# Aquila-2019-ex.net
KiCad netlist of a schematic drawn in EAGLE
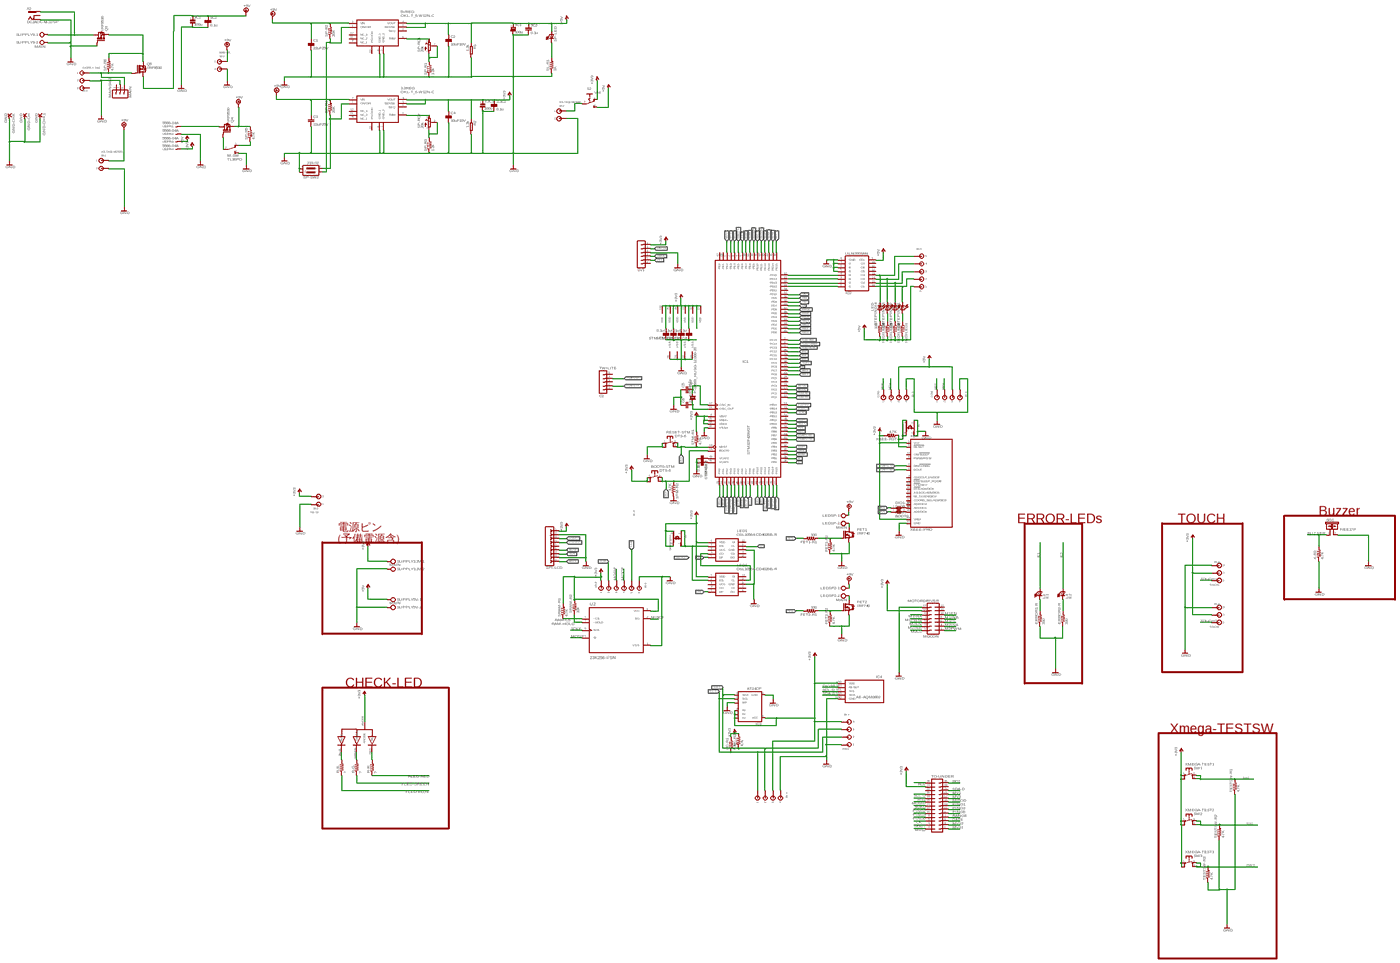
[diagram p0: schematic, sheet 1, overview]
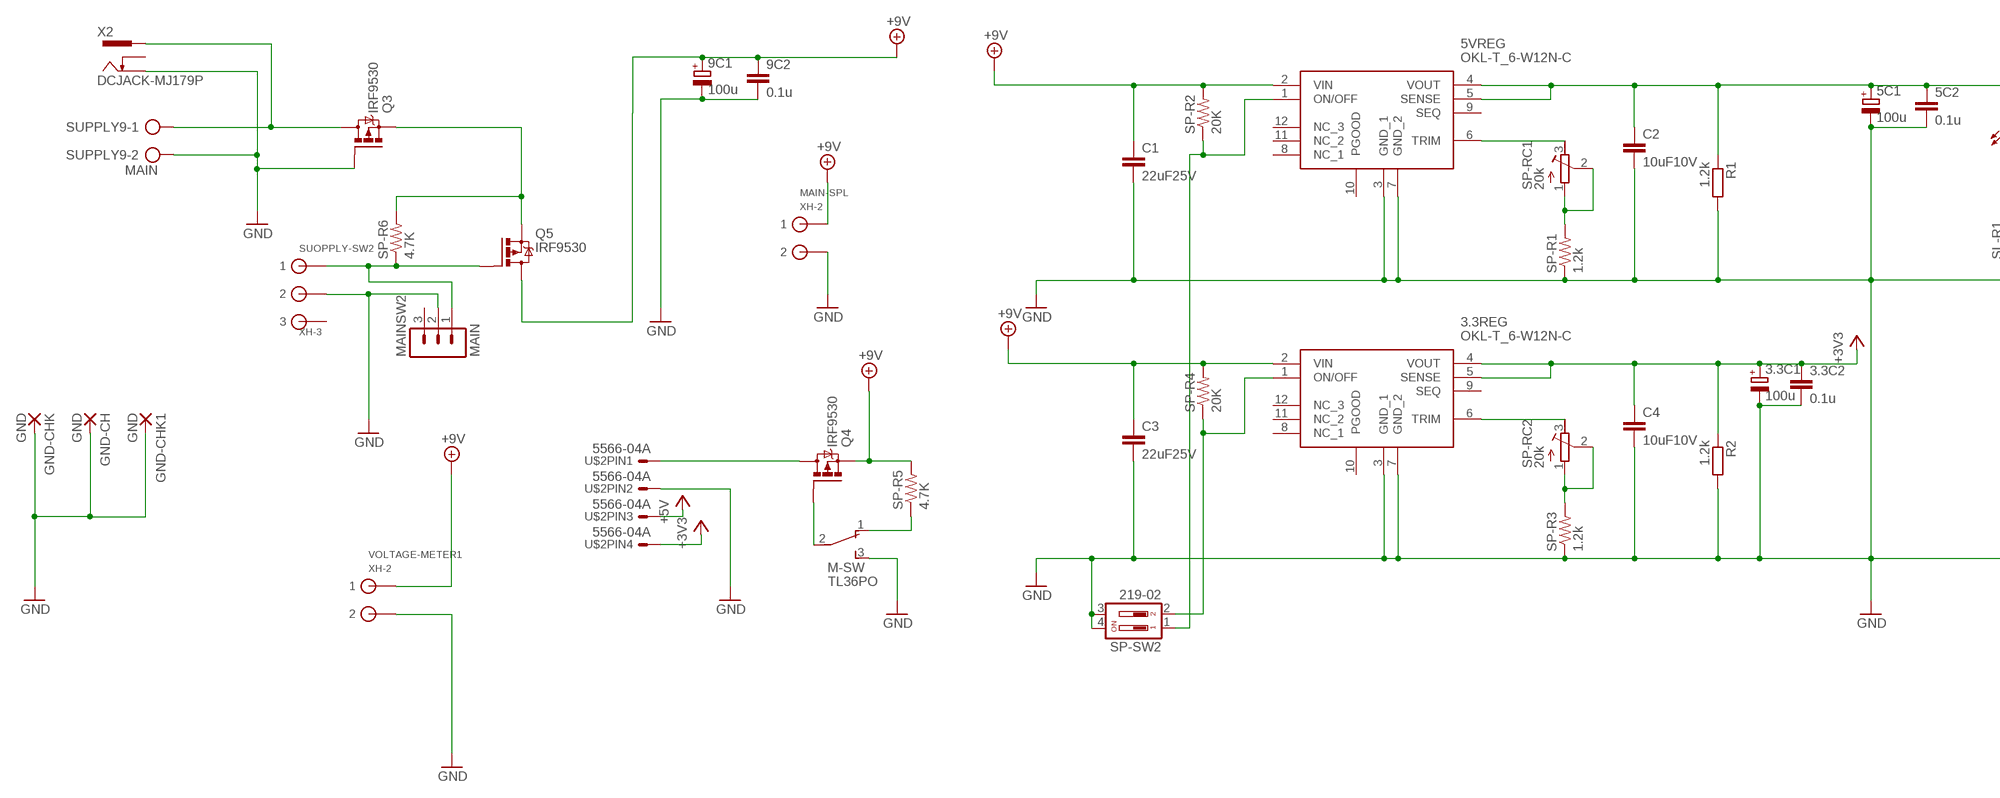
[diagram p1: schematic, sheet 1, part 1 of 5]
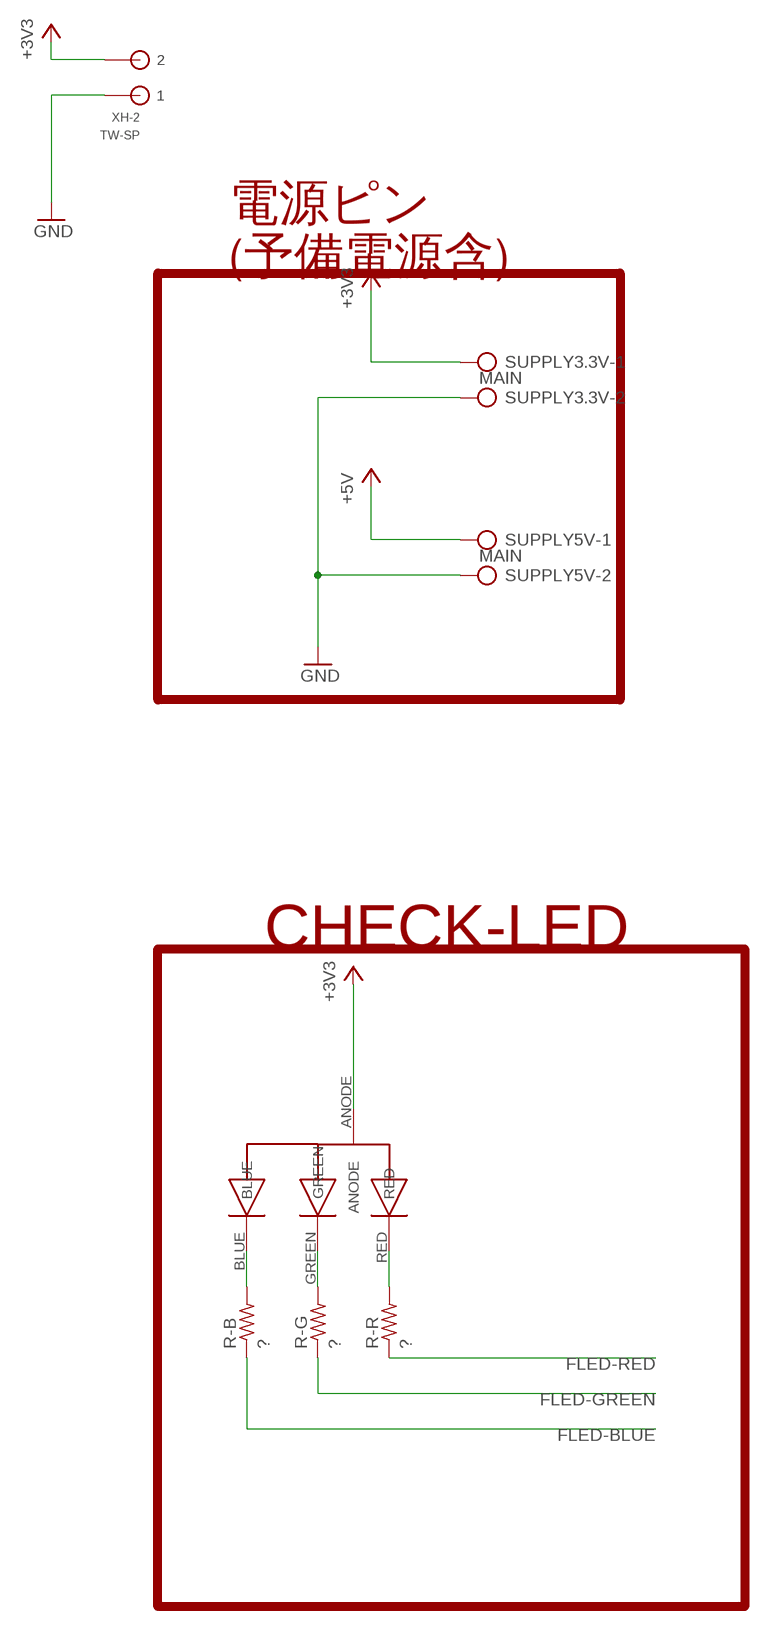
[diagram p2: schematic, sheet 1, part 2 of 5]
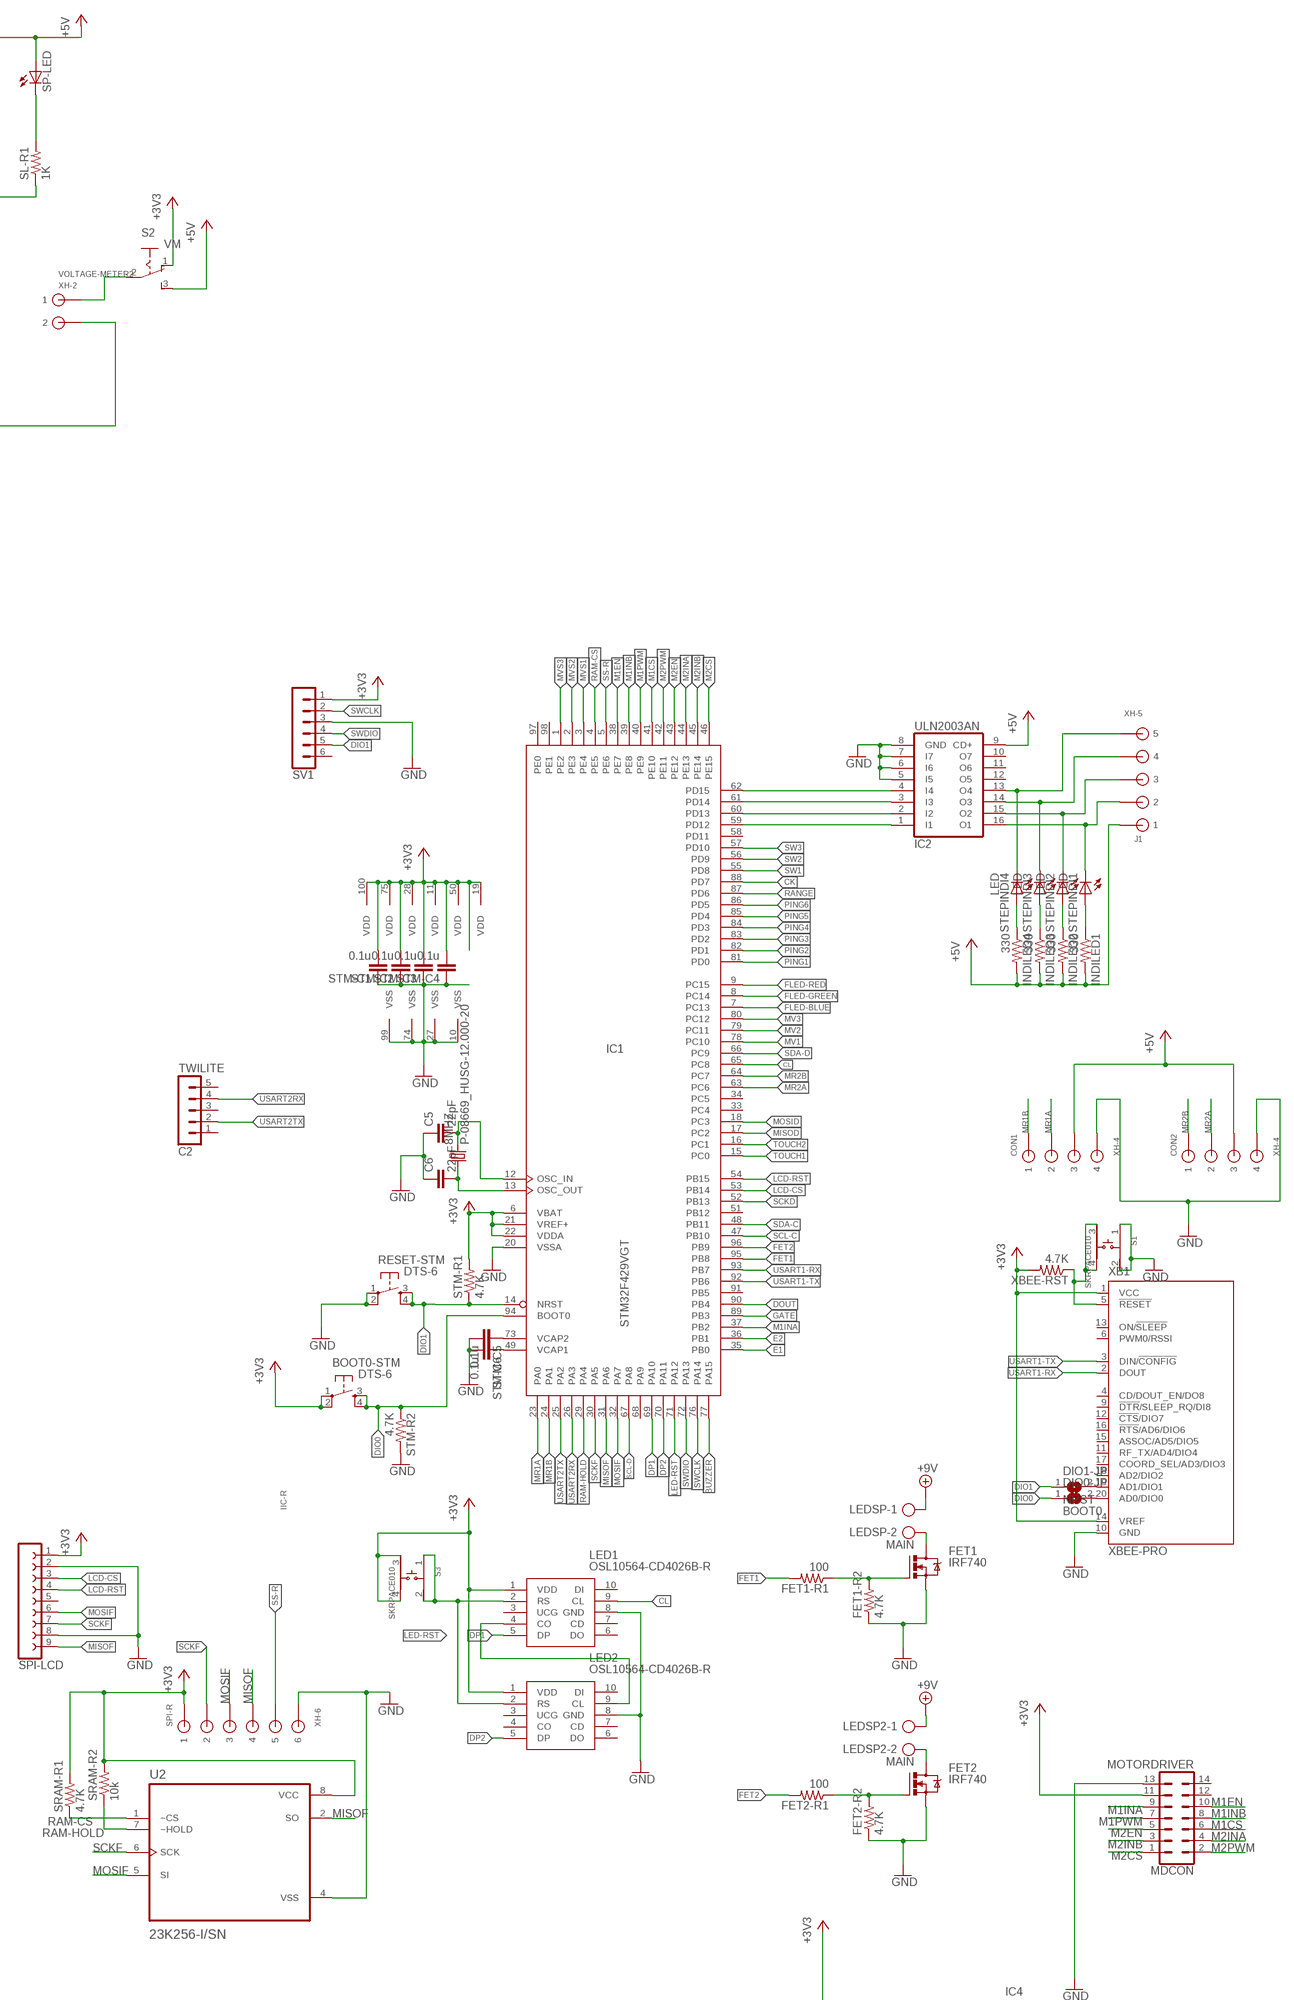
[diagram p3: schematic, sheet 1, part 3 of 5]
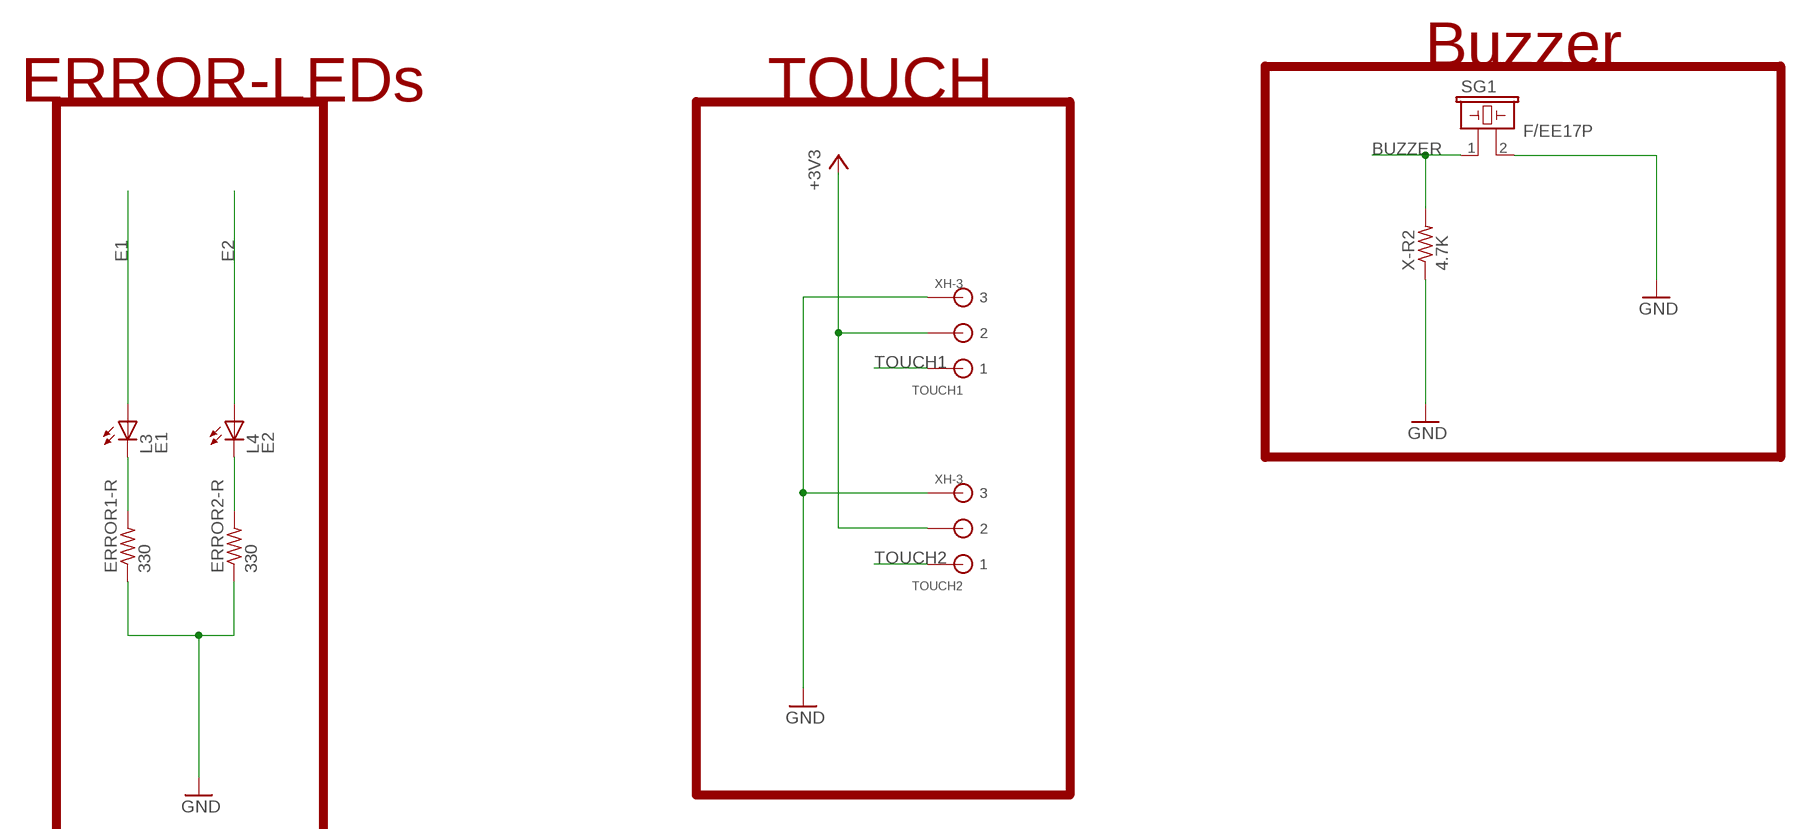
[diagram p4: schematic, sheet 1, part 4 of 5]
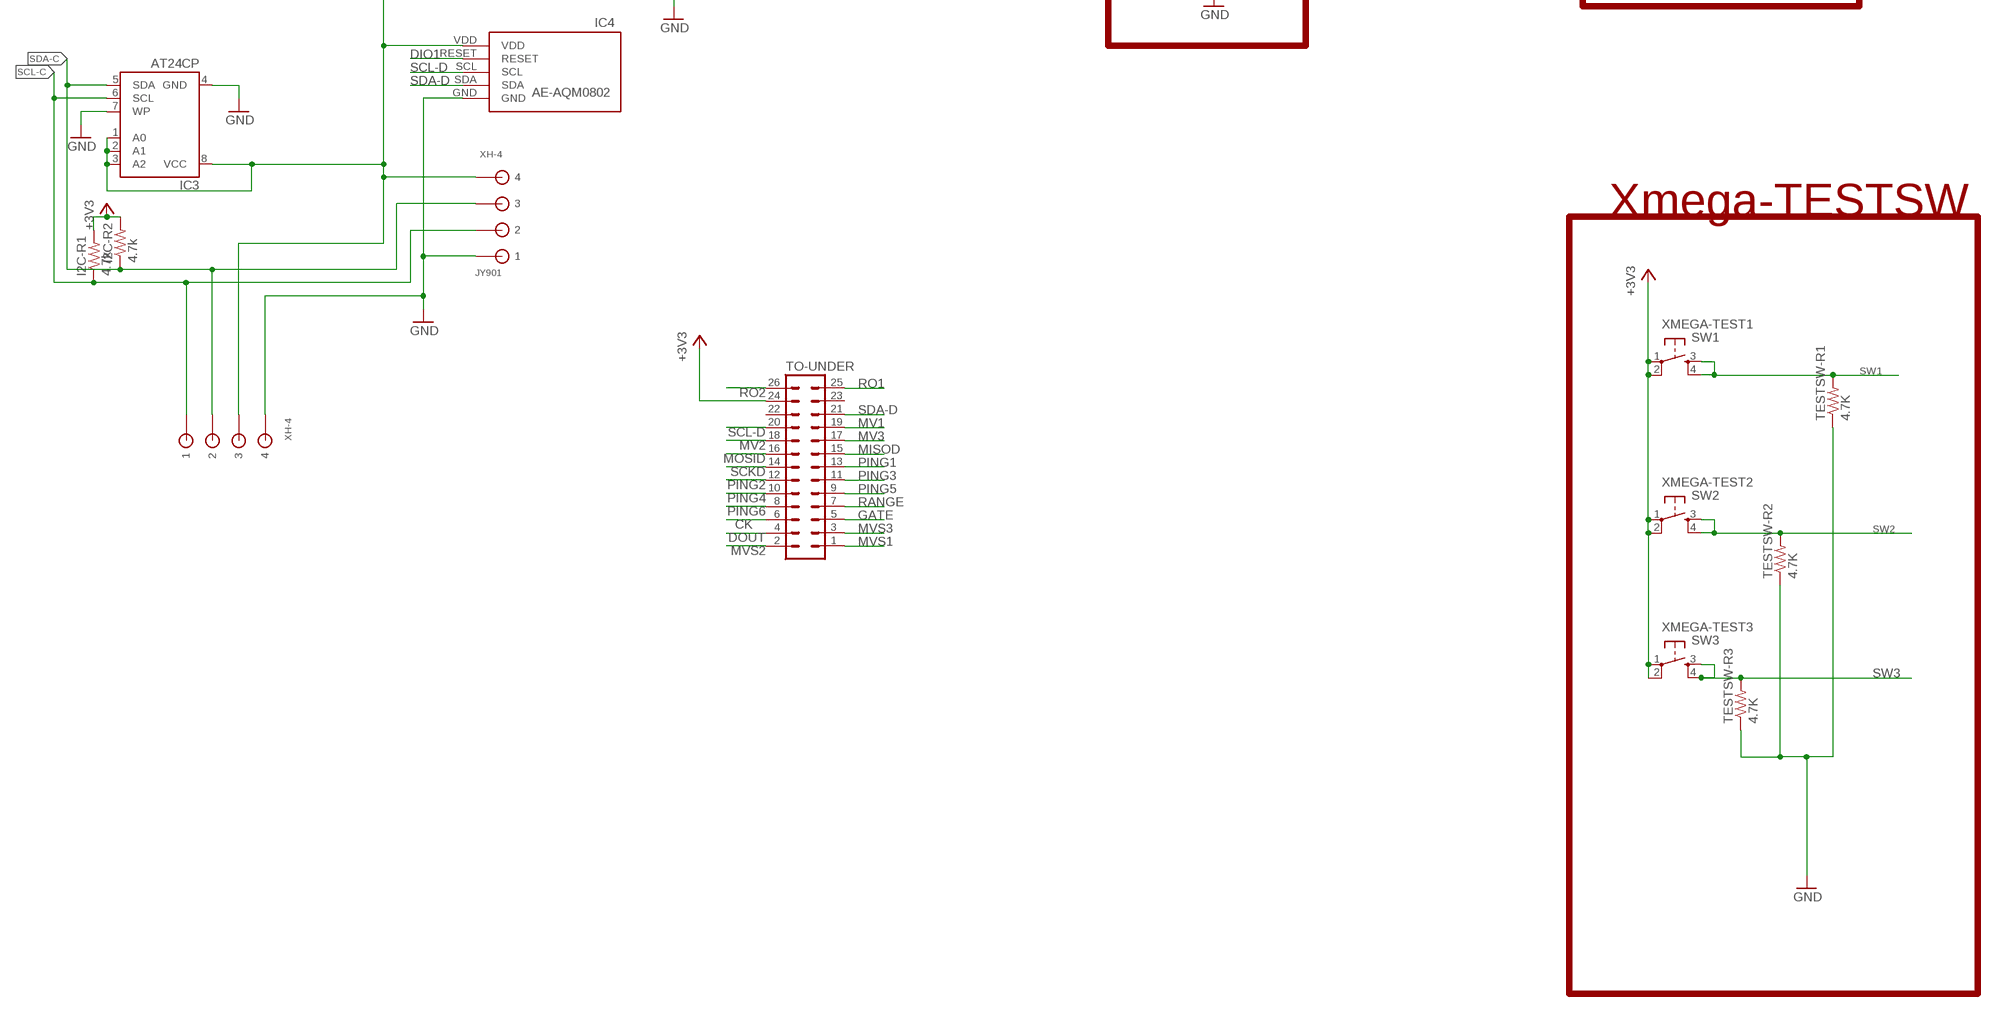
[diagram p5: schematic, sheet 1, part 5 of 5]

(export (version "E")
  (design (tool "Eeschema 10.0.6"))
  (components
    (comp (ref "3.3C1")
      (value "100u")
      (footprint "eagle-import:D_7343-31R")
      (fields (field (name "SPICEPREFIX") "B"))
      (libsource (lib "eagle-import") (part "CPOL-EUD/7343-31R"))
    )
    (comp (ref "3.3C2")
      (value "0.1u")
      (footprint "eagle-import:C0805")
      (fields (field (name "SPICEPREFIX") "B"))
      (libsource (lib "eagle-import") (part "C-EUC0805"))
    )
    (comp (ref "3.3REG")
      (value "OKL-T_6-W12N-C")
      (footprint "eagle-import:OKL-T_3-W5")
      (fields (field (name "ARROW_PART_NUMBER") "OKL-T/6-W12N-C") (field (name "RS_PART_NUMBER") "1736944P"))
      (libsource (lib "eagle-import") (part "OKL-T_6-W12N-C"))
    )
    (comp (ref "5C1")
      (value "100u")
      (footprint "eagle-import:D_7343-31R")
      (fields (field (name "SPICEPREFIX") "B"))
      (libsource (lib "eagle-import") (part "CPOL-EUD/7343-31R"))
    )
    (comp (ref "5C2")
      (value "0.1u")
      (footprint "eagle-import:C0805")
      (fields (field (name "SPICEPREFIX") "B"))
      (libsource (lib "eagle-import") (part "C-EUC0805"))
    )
    (comp (ref "5VREG")
      (value "OKL-T_6-W12N-C")
      (footprint "eagle-import:OKL-T_3-W5")
      (fields (field (name "ARROW_PART_NUMBER") "OKL-T/6-W12N-C") (field (name "RS_PART_NUMBER") "1736944P"))
      (libsource (lib "eagle-import") (part "OKL-T_6-W12N-C"))
    )
    (comp (ref "8MHZ")
      (value "P-08669_HUSG-12.000-20")
      (footprint "eagle-import:HC49U-V")
      (libsource (lib "eagle-import") (part "P-08669_HUSG-12.000-20"))
    )
    (comp (ref "9C1")
      (value "100u")
      (footprint "eagle-import:D_7343-31R")
      (fields (field (name "SPICEPREFIX") "B"))
      (libsource (lib "eagle-import") (part "CPOL-EUD/7343-31R"))
    )
    (comp (ref "9C2")
      (value "0.1u")
      (footprint "eagle-import:C0805")
      (fields (field (name "SPICEPREFIX") "B"))
      (libsource (lib "eagle-import") (part "C-EUC0805"))
    )
    (comp (ref "BOOT0-STM")
      (value "DTS-6")
      (footprint "eagle-import:DTS-6")
      (libsource (lib "eagle-import") (part "DTS-6"))
    )
    (comp (ref "C1")
      (value "22uF25V")
      (footprint "eagle-import:C2012")
      (libsource (lib "eagle-import") (part "resistor_348_C-EUC2012"))
    )
    (comp (ref "C2")
      (value "10uF10V")
      (footprint "eagle-import:C2012")
      (libsource (lib "eagle-import") (part "resistor_348_C-EUC2012"))
    )
    (comp (ref "C3")
      (value "22uF25V")
      (footprint "eagle-import:C2012")
      (libsource (lib "eagle-import") (part "resistor_348_C-EUC2012"))
    )
    (comp (ref "C4")
      (value "10uF10V")
      (footprint "eagle-import:C2012")
      (libsource (lib "eagle-import") (part "resistor_348_C-EUC2012"))
    )
    (comp (ref "C5")
      (value "22pF")
      (footprint "eagle-import:C1608")
      (libsource (lib "eagle-import") (part "resistor_348_C-EUC1608"))
    )
    (comp (ref "C6")
      (value "22pF")
      (footprint "eagle-import:C1608")
      (libsource (lib "eagle-import") (part "resistor_348_C-EUC1608"))
    )
    (comp (ref "CHECKLED")
      (value "OSTA71A1D-A")
      (footprint "eagle-import:OSTA71A1D-A")
      (libsource (lib "eagle-import") (part "OSTA71A1D-A"))
    )
    (comp (ref "CON1")
      (value "XH-4")
      (footprint "eagle-import:CON4")
      (libsource (lib "eagle-import") (part "XH-4"))
    )
    (comp (ref "CON2")
      (value "XH-4")
      (footprint "eagle-import:CON4")
      (libsource (lib "eagle-import") (part "XH-4"))
    )
    (comp (ref "DIO0-JP")
      (value "BOOT0")
      (footprint "eagle-import:SJ")
      (libsource (lib "eagle-import") (part "SJ"))
    )
    (comp (ref "DIO1-JP")
      (value "NRST")
      (footprint "eagle-import:SJ")
      (libsource (lib "eagle-import") (part "SJ"))
    )
    (comp (ref "ERROR1-R")
      (value "330")
      (footprint "eagle-import:R0805")
      (libsource (lib "eagle-import") (part "R-US_R0805"))
    )
    (comp (ref "ERROR2-R")
      (value "330")
      (footprint "eagle-import:R0805")
      (libsource (lib "eagle-import") (part "R-US_R0805"))
    )
    (comp (ref "FET1")
      (value "IRF740")
      (footprint "eagle-import:TO220BV")
      (libsource (lib "eagle-import") (part "IRF740"))
    )
    (comp (ref "FET1-R1")
      (value "100")
      (footprint "eagle-import:R0805")
      (libsource (lib "eagle-import") (part "R-US_R0805"))
    )
    (comp (ref "FET1-R2")
      (value "4.7K")
      (footprint "eagle-import:R0805")
      (libsource (lib "eagle-import") (part "R-US_R0805"))
    )
    (comp (ref "FET2")
      (value "IRF740")
      (footprint "eagle-import:TO220BV")
      (libsource (lib "eagle-import") (part "IRF740"))
    )
    (comp (ref "FET2-R1")
      (value "100")
      (footprint "eagle-import:R0805")
      (libsource (lib "eagle-import") (part "R-US_R0805"))
    )
    (comp (ref "FET2-R2")
      (value "4.7K")
      (footprint "eagle-import:R0805")
      (libsource (lib "eagle-import") (part "R-US_R0805"))
    )
    (comp (ref "GND-CH")
      (value "GND")
      (footprint "eagle-import:SMD2,54-5,08")
      (libsource (lib "eagle-import") (part "SMD5"))
    )
    (comp (ref "GND-CHK")
      (value "GND")
      (footprint "eagle-import:2,15_1,0")
      (libsource (lib "eagle-import") (part "2,15/1,0"))
    )
    (comp (ref "GND-CHK1")
      (value "GND")
      (footprint "eagle-import:2,15_1,0")
      (libsource (lib "eagle-import") (part "2,15/1,0"))
    )
    (comp (ref "I2C-R1")
      (value "4.7k")
      (footprint "eagle-import:R0805")
      (libsource (lib "eagle-import") (part "R-US_R0805"))
    )
    (comp (ref "I2C-R2")
      (value "4.7k")
      (footprint "eagle-import:R0805")
      (libsource (lib "eagle-import") (part "R-US_R0805"))
    )
    (comp (ref "IC1")
      (value "STM32F429VGT")
      (footprint "eagle-import:LQFP100")
      (libsource (lib "eagle-import") (part "STM32F429VTG"))
    )
    (comp (ref "IC2")
      (value "ULN2003AN")
      (footprint "eagle-import:DIL16")
      (fields (field (name "MF") "STMicroelectronics") (field (name "MP") "ULN2003A"))
      (libsource (lib "eagle-import") (part "ULN2003AN"))
    )
    (comp (ref "IC3")
      (value "AT24CP")
      (footprint "eagle-import:DIL08")
      (fields (field (name "MPN") "AT24C1024BW-SH-B"))
      (libsource (lib "eagle-import") (part "AT24CP"))
    )
    (comp (ref "IC4")
      (value "AE-AQM0802")
      (footprint "eagle-import:AE-AQM0802")
      (libsource (lib "eagle-import") (part "AE-AQM0802"))
    )
    (comp (ref "IIC-R")
      (value "XH-4")
      (footprint "eagle-import:CON4")
      (libsource (lib "eagle-import") (part "XH-4"))
    )
    (comp (ref "INDILED1")
      (value "330")
      (footprint "eagle-import:R0805")
      (libsource (lib "eagle-import") (part "R-US_R0805"))
    )
    (comp (ref "INDILED2")
      (value "330")
      (footprint "eagle-import:R0805")
      (libsource (lib "eagle-import") (part "R-US_R0805"))
    )
    (comp (ref "INDILED3")
      (value "330")
      (footprint "eagle-import:R0805")
      (libsource (lib "eagle-import") (part "R-US_R0805"))
    )
    (comp (ref "INDILED4")
      (value "330")
      (footprint "eagle-import:R0805")
      (libsource (lib "eagle-import") (part "R-US_R0805"))
    )
    (comp (ref "J1")
      (value "XH-5")
      (footprint "eagle-import:CON5")
      (libsource (lib "eagle-import") (part "XH-5"))
    )
    (comp (ref "JY901")
      (value "XH-4")
      (footprint "eagle-import:CON4")
      (libsource (lib "eagle-import") (part "XH-4"))
    )
    (comp (ref "L3")
      (value "E1")
      (footprint "eagle-import:LED5MM")
      (libsource (lib "eagle-import") (part "LED5MM"))
    )
    (comp (ref "L4")
      (value "E2")
      (footprint "eagle-import:LED5MM")
      (libsource (lib "eagle-import") (part "LED5MM"))
    )
    (comp (ref "LED1")
      (value "OSL10564-CD4026B-R")
      (footprint "eagle-import:DIPS1524W50P254L1260H800Q10N")
      (libsource (lib "eagle-import") (part "OSL10564-CD4026B-R"))
    )
    (comp (ref "LED2")
      (value "OSL10564-CD4026B-R")
      (footprint "eagle-import:DIPS1524W50P254L1260H800Q10N")
      (libsource (lib "eagle-import") (part "OSL10564-CD4026B-R"))
    )
    (comp (ref "LEDSP")
      (value "MAIN")
      (footprint "eagle-import:AK500_2")
      (libsource (lib "eagle-import") (part "AK500/2"))
    )
    (comp (ref "LEDSP2")
      (value "MAIN")
      (footprint "eagle-import:AK500_2")
      (libsource (lib "eagle-import") (part "AK500/2"))
    )
    (comp (ref "M-SW")
      (value "TL36PO")
      (footprint "eagle-import:TL3XPO")
      (libsource (lib "eagle-import") (part "TL36PO"))
    )
    (comp (ref "MAIN-SPL")
      (value "XH-2")
      (footprint "eagle-import:CON2")
      (libsource (lib "eagle-import") (part "forprint_XH-2"))
    )
    (comp (ref "MAINSW2")
      (value "MAIN")
      (footprint "eagle-import:MA03-1")
      (libsource (lib "eagle-import") (part "MA03-1"))
    )
    (comp (ref "MOTORDRIVER")
      (value "MDCON")
      (footprint "eagle-import:ML14")
      (libsource (lib "eagle-import") (part "ML14"))
    )
    (comp (ref "Q3")
      (value "IRF9530")
      (footprint "eagle-import:TO220BV")
      (libsource (lib "eagle-import") (part "IRF9530"))
    )
    (comp (ref "Q4")
      (value "IRF9530")
      (footprint "eagle-import:TO220BV")
      (libsource (lib "eagle-import") (part "IRF9530"))
    )
    (comp (ref "Q5")
      (value "IRF9530")
      (footprint "eagle-import:TO220BV")
      (libsource (lib "eagle-import") (part "IRF9530"))
    )
    (comp (ref "R-B")
      (value "?")
      (footprint "eagle-import:R0805")
      (libsource (lib "eagle-import") (part "R-US_R0805"))
    )
    (comp (ref "R-G")
      (value "?")
      (footprint "eagle-import:R0805")
      (libsource (lib "eagle-import") (part "R-US_R0805"))
    )
    (comp (ref "R-R")
      (value "?")
      (footprint "eagle-import:R0805")
      (libsource (lib "eagle-import") (part "R-US_R0805"))
    )
    (comp (ref "R1")
      (value "1.2k")
      (footprint "eagle-import:0204_7")
      (libsource (lib "eagle-import") (part "R-EU_0204/7"))
    )
    (comp (ref "R2")
      (value "1.2k")
      (footprint "eagle-import:0204_7")
      (libsource (lib "eagle-import") (part "R-EU_0204/7"))
    )
    (comp (ref "RESET-STM")
      (value "DTS-6")
      (footprint "eagle-import:DTS-6")
      (libsource (lib "eagle-import") (part "DTS-6"))
    )
    (comp (ref "S1")
      (value "SKRPACE010")
      (footprint "eagle-import:SW_SKRPACE010")
      (fields (field (name "MF") "ALPS"))
      (libsource (lib "eagle-import") (part "SKRPACE010"))
    )
    (comp (ref "S2")
      (value "VM")
      (footprint "eagle-import:M251")
      (libsource (lib "eagle-import") (part "M251"))
    )
    (comp (ref "S3")
      (value "SKRPACE010")
      (footprint "eagle-import:SW_SKRPACE010")
      (fields (field (name "MF") "ALPS"))
      (libsource (lib "eagle-import") (part "SKRPACE010"))
    )
    (comp (ref "SG1")
      (value "F/EE17P")
      (footprint "eagle-import:F_EE17P")
      (libsource (lib "eagle-import") (part "F/EE17P"))
    )
    (comp (ref "SL-R1")
      (value "1K")
      (footprint "eagle-import:R0805")
      (libsource (lib "eagle-import") (part "R-US_R0805"))
    )
    (comp (ref "SP-LED")
      (value "LEDCHIPLED_0805")
      (footprint "eagle-import:CHIPLED_0805")
      (libsource (lib "eagle-import") (part "led_LEDCHIPLED_0805"))
    )
    (comp (ref "SP-R1")
      (value "1.2k")
      (footprint "eagle-import:R0805")
      (libsource (lib "eagle-import") (part "R-US_R0805"))
    )
    (comp (ref "SP-R2")
      (value "20K")
      (footprint "eagle-import:R0805")
      (libsource (lib "eagle-import") (part "R-US_R0805"))
    )
    (comp (ref "SP-R3")
      (value "1.2k")
      (footprint "eagle-import:R0805")
      (libsource (lib "eagle-import") (part "R-US_R0805"))
    )
    (comp (ref "SP-R4")
      (value "20K")
      (footprint "eagle-import:R0805")
      (libsource (lib "eagle-import") (part "R-US_R0805"))
    )
    (comp (ref "SP-R5")
      (value "4.7K")
      (footprint "eagle-import:R0805")
      (libsource (lib "eagle-import") (part "R-US_R0805"))
    )
    (comp (ref "SP-R6")
      (value "4.7K")
      (footprint "eagle-import:R0805")
      (libsource (lib "eagle-import") (part "R-US_R0805"))
    )
    (comp (ref "SP-RC1")
      (value "20k")
      (footprint "eagle-import:RTRIM3296W")
      (libsource (lib "eagle-import") (part "R-TRIMM3296W"))
    )
    (comp (ref "SP-RC2")
      (value "20k")
      (footprint "eagle-import:RTRIM3296W")
      (libsource (lib "eagle-import") (part "R-TRIMM3296W"))
    )
    (comp (ref "SP-SW2")
      (value "219-02")
      (footprint "eagle-import:CTS-219-02")
      (libsource (lib "eagle-import") (part "219-02"))
    )
    (comp (ref "SPI-LCD")
      (value "FE09-1")
      (footprint "eagle-import:FE09")
      (libsource (lib "eagle-import") (part "FE09-1"))
    )
    (comp (ref "SPI-R")
      (value "XH-6")
      (footprint "eagle-import:CON6")
      (libsource (lib "eagle-import") (part "XH-6"))
    )
    (comp (ref "SRAM-R1")
      (value "4.7K")
      (footprint "eagle-import:R0805")
      (libsource (lib "eagle-import") (part "R-US_R0805"))
    )
    (comp (ref "SRAM-R2")
      (value "10k")
      (footprint "eagle-import:R0805")
      (libsource (lib "eagle-import") (part "R-US_R0805"))
    )
    (comp (ref "STEPINDI1")
      (value "LED")
      (footprint "eagle-import:CHIPLED_0805")
      (libsource (lib "eagle-import") (part "led_LEDCHIPLED_0805"))
    )
    (comp (ref "STEPINDI2")
      (value "LED")
      (footprint "eagle-import:CHIPLED_0805")
      (libsource (lib "eagle-import") (part "led_LEDCHIPLED_0805"))
    )
    (comp (ref "STEPINDI3")
      (value "LED")
      (footprint "eagle-import:CHIPLED_0805")
      (libsource (lib "eagle-import") (part "led_LEDCHIPLED_0805"))
    )
    (comp (ref "STEPINDI4")
      (value "LED")
      (footprint "eagle-import:CHIPLED_0805")
      (libsource (lib "eagle-import") (part "led_LEDCHIPLED_0805"))
    )
    (comp (ref "STM-C1")
      (value "0.1u")
      (footprint "eagle-import:C0805")
      (libsource (lib "eagle-import") (part "C-EUC0805"))
    )
    (comp (ref "STM-C2")
      (value "0.1u")
      (footprint "eagle-import:C0805")
      (libsource (lib "eagle-import") (part "C-EUC0805"))
    )
    (comp (ref "STM-C3")
      (value "0.1u")
      (footprint "eagle-import:C0805")
      (libsource (lib "eagle-import") (part "C-EUC0805"))
    )
    (comp (ref "STM-C4")
      (value "0.1u")
      (footprint "eagle-import:C0805")
      (libsource (lib "eagle-import") (part "C-EUC0805"))
    )
    (comp (ref "STM-C5")
      (value "0.1u")
      (footprint "eagle-import:C0805")
      (libsource (lib "eagle-import") (part "C-EUC0805"))
    )
    (comp (ref "STM-C6")
      (value "0.1u")
      (footprint "eagle-import:C0805")
      (libsource (lib "eagle-import") (part "C-EUC0805"))
    )
    (comp (ref "STM-R1")
      (value "4.7K")
      (footprint "eagle-import:R0805")
      (libsource (lib "eagle-import") (part "R-US_R0805"))
    )
    (comp (ref "STM-R2")
      (value "4.7K")
      (footprint "eagle-import:R0805")
      (libsource (lib "eagle-import") (part "R-US_R0805"))
    )
    (comp (ref "SUOPPLY-SW2")
      (value "XH-3")
      (footprint "eagle-import:CON3")
      (libsource (lib "eagle-import") (part "XH-3"))
    )
    (comp (ref "SUPPLY3.3V")
      (value "MAIN")
      (footprint "eagle-import:AK500_2")
      (libsource (lib "eagle-import") (part "AK500/2"))
    )
    (comp (ref "SUPPLY5V")
      (value "MAIN")
      (footprint "eagle-import:AK500_2")
      (libsource (lib "eagle-import") (part "AK500/2"))
    )
    (comp (ref "SUPPLY9")
      (value "MAIN")
      (footprint "eagle-import:AK500_2")
      (libsource (lib "eagle-import") (part "AK500/2"))
    )
    (comp (ref "SV1")
      (value "MA06-1")
      (footprint "eagle-import:MA06-1")
      (libsource (lib "eagle-import") (part "MA06-1"))
    )
    (comp (ref "TESTSW-R1")
      (value "4.7K")
      (footprint "eagle-import:R0805")
      (libsource (lib "eagle-import") (part "R-US_R0805"))
    )
    (comp (ref "TESTSW-R2")
      (value "4.7K")
      (footprint "eagle-import:R0805")
      (libsource (lib "eagle-import") (part "R-US_R0805"))
    )
    (comp (ref "TESTSW-R3")
      (value "4.7K")
      (footprint "eagle-import:R0805")
      (libsource (lib "eagle-import") (part "R-US_R0805"))
    )
    (comp (ref "TO-UNDER")
      (value "ML26")
      (footprint "eagle-import:ML26")
      (libsource (lib "eagle-import") (part "ML26"))
    )
    (comp (ref "TOUCH1")
      (value "XH-3")
      (footprint "eagle-import:CON3")
      (libsource (lib "eagle-import") (part "XH-3"))
    )
    (comp (ref "TOUCH2")
      (value "XH-3")
      (footprint "eagle-import:CON3")
      (libsource (lib "eagle-import") (part "XH-3"))
    )
    (comp (ref "TW-SP")
      (value "XH-2")
      (footprint "eagle-import:CON2")
      (libsource (lib "eagle-import") (part "XH-2"))
    )
    (comp (ref "TWILITE")
      (value "C2")
      (footprint "eagle-import:MA05-1")
      (libsource (lib "eagle-import") (part "MA05-1"))
    )
    (comp (ref "U$2")
      (value "5566-04A")
      (footprint "eagle-import:5566-04A")
      (libsource (lib "eagle-import") (part "5566-04A"))
    )
    (comp (ref "U2")
      (value "23K256-I/SN")
      (footprint "eagle-import:SOIC127P600X175-8N")
      (fields (field (name "MF") "Microchip"))
      (libsource (lib "eagle-import") (part "23K256-I/SN"))
    )
    (comp (ref "VOLTAGE-METER1")
      (value "XH-2")
      (footprint "eagle-import:CON2")
      (libsource (lib "eagle-import") (part "forprint_XH-2"))
    )
    (comp (ref "VOLTAGE-METER2")
      (value "XH-2")
      (footprint "eagle-import:CON2")
      (libsource (lib "eagle-import") (part "forprint_XH-2"))
    )
    (comp (ref "X-R2")
      (value "4.7K")
      (footprint "eagle-import:R0805")
      (libsource (lib "eagle-import") (part "R-US_R0805"))
    )
    (comp (ref "X2")
      (value "DCJACK-MJ179P")
      (footprint "eagle-import:MJ-179P")
      (libsource (lib "eagle-import") (part "DCJACK-MJ179P"))
    )
    (comp (ref "XB1")
      (value "XBEE-PRO")
      (footprint "eagle-import:XBEE-PRO")
      (fields (field (name "MPN") "XBP24-AWI-001"))
      (libsource (lib "eagle-import") (part "XBEE-PRO"))
    )
    (comp (ref "XBEE-RST")
      (value "4.7K")
      (footprint "eagle-import:R0805")
      (libsource (lib "eagle-import") (part "R-US_R0805"))
    )
    (comp (ref "XMEGA-TEST1")
      (value "SW1")
      (footprint "eagle-import:DTS-6")
      (libsource (lib "eagle-import") (part "DTS-6"))
    )
    (comp (ref "XMEGA-TEST2")
      (value "SW2")
      (footprint "eagle-import:DTS-6")
      (libsource (lib "eagle-import") (part "DTS-6"))
    )
    (comp (ref "XMEGA-TEST3")
      (value "SW3")
      (footprint "eagle-import:DTS-6")
      (libsource (lib "eagle-import") (part "DTS-6"))
    )
  )
  (nets
    (net (code "1") (name "+3V3") (class "Default")
      (node (ref "3.3C1") (pin "+") (pinfunction "+_+") (pintype "passive"))
      (node (ref "3.3C2") (pin "1") (pinfunction "1_1") (pintype "passive"))
      (node (ref "3.3REG") (pin "4") (pinfunction "VOUT_4") (pintype "bidirectional"))
      (node (ref "3.3REG") (pin "5") (pinfunction "SENSE_5") (pintype "bidirectional"))
      (node (ref "BOOT0-STM") (pin "1") (pinfunction "1_1") (pintype "passive"))
      (node (ref "BOOT0-STM") (pin "2") (pinfunction "2_2") (pintype "passive"))
      (node (ref "C4") (pin "1") (pinfunction "1_1") (pintype "passive"))
      (node (ref "CHECKLED") (pin "ANODE") (pinfunction "ANODE_ANODE") (pintype "bidirectional"))
      (node (ref "I2C-R1") (pin "2") (pinfunction "2_2") (pintype "passive"))
      (node (ref "I2C-R2") (pin "2") (pinfunction "2_2") (pintype "passive"))
      (node (ref "IC1") (pin "100") (pinfunction "VDD_100") (pintype "power_in"))
      (node (ref "IC1") (pin "11") (pinfunction "VDD_11") (pintype "power_in"))
      (node (ref "IC1") (pin "19") (pinfunction "VDD_19") (pintype "power_in"))
      (node (ref "IC1") (pin "21") (pinfunction "VREF+_21") (pintype "power_in"))
      (node (ref "IC1") (pin "22") (pinfunction "VDDA_22") (pintype "power_in"))
      (node (ref "IC1") (pin "28") (pinfunction "VDD_28") (pintype "power_in"))
      (node (ref "IC1") (pin "50") (pinfunction "VDD_50") (pintype "power_in"))
      (node (ref "IC1") (pin "6") (pinfunction "VBAT_6") (pintype "power_in"))
      (node (ref "IC1") (pin "75") (pinfunction "VDD_75") (pintype "power_in"))
      (node (ref "IC3") (pin "1") (pinfunction "A0_1") (pintype "input"))
      (node (ref "IC3") (pin "2") (pinfunction "A1_2") (pintype "input"))
      (node (ref "IC3") (pin "3") (pinfunction "A2_3") (pintype "input"))
      (node (ref "IC3") (pin "8") (pinfunction "VCC_8") (pintype "power_in"))
      (node (ref "IC4") (pin "VDD") (pinfunction "VDD_VDD") (pintype "bidirectional"))
      (node (ref "IIC-R") (pin "P$3") (pinfunction "3_P$3") (pintype "bidirectional"))
      (node (ref "JY901") (pin "P$4") (pinfunction "4_P$4") (pintype "bidirectional"))
      (node (ref "LED1") (pin "1") (pinfunction "VDD_1") (pintype "bidirectional"))
      (node (ref "LED2") (pin "1") (pinfunction "VDD_1") (pintype "bidirectional"))
      (node (ref "MOTORDRIVER") (pin "11") (pinfunction "11_11") (pintype "passive"))
      (node (ref "R2") (pin "1") (pinfunction "1_1") (pintype "passive"))
      (node (ref "S2") (pin "1") (pinfunction "O_1") (pintype "passive"))
      (node (ref "S3") (pin "3") (pinfunction "3_3") (pintype "bidirectional"))
      (node (ref "S3") (pin "4") (pinfunction "4_4") (pintype "bidirectional"))
      (node (ref "SPI-LCD") (pin "1") (pinfunction "1_1") (pintype "passive"))
      (node (ref "SPI-R") (pin "P$1") (pinfunction "1_P$1") (pintype "bidirectional"))
      (node (ref "SRAM-R1") (pin "2") (pinfunction "2_2") (pintype "passive"))
      (node (ref "SRAM-R2") (pin "2") (pinfunction "2_2") (pintype "passive"))
      (node (ref "STM-C1") (pin "2") (pinfunction "2_2") (pintype "passive"))
      (node (ref "STM-C2") (pin "2") (pinfunction "2_2") (pintype "passive"))
      (node (ref "STM-C3") (pin "2") (pinfunction "2_2") (pintype "passive"))
      (node (ref "STM-C4") (pin "2") (pinfunction "2_2") (pintype "passive"))
      (node (ref "STM-R1") (pin "2") (pinfunction "2_2") (pintype "passive"))
      (node (ref "SUPPLY3.3V") (pin "1") (pinfunction "KL_1") (pintype "passive"))
      (node (ref "SV1") (pin "1") (pinfunction "1_1") (pintype "passive"))
      (node (ref "TO-UNDER") (pin "24") (pinfunction "24_24") (pintype "passive"))
      (node (ref "TOUCH1") (pin "P$2") (pinfunction "2_P$2") (pintype "bidirectional"))
      (node (ref "TOUCH2") (pin "P$2") (pinfunction "2_P$2") (pintype "bidirectional"))
      (node (ref "TW-SP") (pin "P$2") (pinfunction "2_P$2") (pintype "bidirectional"))
      (node (ref "U$2") (pin "4") (pinfunction "S_4") (pintype "passive"))
      (node (ref "U2") (pin "8") (pinfunction "VCC_8") (pintype "power_in"))
      (node (ref "XB1") (pin "1") (pinfunction "VCC_1") (pintype "power_in"))
      (node (ref "XB1") (pin "14") (pinfunction "VREF_14") (pintype "input"))
      (node (ref "XBEE-RST") (pin "2") (pinfunction "2_2") (pintype "passive"))
      (node (ref "XMEGA-TEST1") (pin "1") (pinfunction "1_1") (pintype "passive"))
      (node (ref "XMEGA-TEST1") (pin "2") (pinfunction "2_2") (pintype "passive"))
      (node (ref "XMEGA-TEST2") (pin "1") (pinfunction "1_1") (pintype "passive"))
      (node (ref "XMEGA-TEST2") (pin "2") (pinfunction "2_2") (pintype "passive"))
      (node (ref "XMEGA-TEST3") (pin "1") (pinfunction "1_1") (pintype "passive"))
      (node (ref "XMEGA-TEST3") (pin "2") (pinfunction "2_2") (pintype "passive"))
    )
    (net (code "2") (name "+5V") (class "Default")
      (node (ref "5C1") (pin "+") (pinfunction "+_+") (pintype "passive"))
      (node (ref "5C2") (pin "1") (pinfunction "1_1") (pintype "passive"))
      (node (ref "5VREG") (pin "4") (pinfunction "VOUT_4") (pintype "bidirectional"))
      (node (ref "5VREG") (pin "5") (pinfunction "SENSE_5") (pintype "bidirectional"))
      (node (ref "C2") (pin "1") (pinfunction "1_1") (pintype "passive"))
      (node (ref "CON1") (pin "P$3") (pinfunction "3_P$3") (pintype "bidirectional"))
      (node (ref "CON2") (pin "P$3") (pinfunction "3_P$3") (pintype "bidirectional"))
      (node (ref "IC2") (pin "9") (pinfunction "CD+_9") (pintype "passive"))
      (node (ref "INDILED1") (pin "2") (pinfunction "2_2") (pintype "passive"))
      (node (ref "INDILED2") (pin "2") (pinfunction "2_2") (pintype "passive"))
      (node (ref "INDILED3") (pin "2") (pinfunction "2_2") (pintype "passive"))
      (node (ref "INDILED4") (pin "2") (pinfunction "2_2") (pintype "passive"))
      (node (ref "J1") (pin "P$1") (pinfunction "1_P$1") (pintype "bidirectional"))
      (node (ref "R1") (pin "1") (pinfunction "1_1") (pintype "passive"))
      (node (ref "S2") (pin "3") (pinfunction "S_3") (pintype "passive"))
      (node (ref "SP-LED") (pin "A") (pinfunction "A_A") (pintype "passive"))
      (node (ref "SUPPLY5V") (pin "1") (pinfunction "KL_1") (pintype "passive"))
      (node (ref "U$2") (pin "3") (pinfunction "S_3") (pintype "passive"))
    )
    (net (code "3") (name "+9V") (class "Default")
      (node (ref "3.3REG") (pin "2") (pinfunction "VIN_2") (pintype "bidirectional"))
      (node (ref "5VREG") (pin "2") (pinfunction "VIN_2") (pintype "bidirectional"))
      (node (ref "9C1") (pin "+") (pinfunction "+_+") (pintype "passive"))
      (node (ref "9C2") (pin "1") (pinfunction "1_1") (pintype "passive"))
      (node (ref "C1") (pin "1") (pinfunction "1_1") (pintype "passive"))
      (node (ref "C3") (pin "1") (pinfunction "1_1") (pintype "passive"))
      (node (ref "LEDSP") (pin "1") (pinfunction "KL_1") (pintype "passive"))
      (node (ref "LEDSP2") (pin "1") (pinfunction "KL_1") (pintype "passive"))
      (node (ref "MAIN-SPL") (pin "P$1") (pinfunction "1_P$1") (pintype "bidirectional"))
      (node (ref "Q4") (pin "S") (pinfunction "S_S") (pintype "passive"))
      (node (ref "Q5") (pin "D") (pinfunction "D_D") (pintype "passive"))
      (node (ref "SP-R2") (pin "2") (pinfunction "2_2") (pintype "passive"))
      (node (ref "SP-R4") (pin "2") (pinfunction "2_2") (pintype "passive"))
      (node (ref "SP-R5") (pin "2") (pinfunction "2_2") (pintype "passive"))
      (node (ref "VOLTAGE-METER1") (pin "P$1") (pinfunction "1_P$1") (pintype "bidirectional"))
    )
    (net (code "4") (name "/RO1") (class "Default")
      (node (ref "TO-UNDER") (pin "25") (pinfunction "25_25") (pintype "passive"))
    )
    (net (code "5") (name "/RO2") (class "Default")
      (node (ref "TO-UNDER") (pin "26") (pinfunction "26_26") (pintype "passive"))
    )
    (net (code "6") (name "BUZZER") (class "Default")
      (node (ref "IC1") (pin "77") (pinfunction "PA15_77") (pintype "bidirectional"))
      (node (ref "SG1") (pin "1") (pinfunction "1_1") (pintype "passive"))
      (node (ref "X-R2") (pin "2") (pinfunction "2_2") (pintype "passive"))
    )
    (net (code "7") (name "CK") (class "Default")
      (node (ref "IC1") (pin "88") (pinfunction "PD7_88") (pintype "bidirectional"))
      (node (ref "TO-UNDER") (pin "6") (pinfunction "6_6") (pintype "passive"))
    )
    (net (code "8") (name "CL") (class "Default")
      (node (ref "IC1") (pin "65") (pinfunction "PC8_65") (pintype "bidirectional"))
      (node (ref "LED1") (pin "9") (pinfunction "CL_9") (pintype "bidirectional"))
    )
    (net (code "9") (name "DIO0") (class "Default")
      (node (ref "BOOT0-STM") (pin "3") (pinfunction "3_3") (pintype "passive"))
      (node (ref "BOOT0-STM") (pin "4") (pinfunction "4_4") (pintype "passive"))
      (node (ref "DIO0-JP") (pin "1") (pinfunction "1_1") (pintype "passive"))
      (node (ref "IC1") (pin "94") (pinfunction "BOOT0_94") (pintype "input"))
      (node (ref "STM-R2") (pin "1") (pinfunction "1_1") (pintype "passive"))
    )
    (net (code "10") (name "DIO1") (class "Default")
      (node (ref "DIO1-JP") (pin "1") (pinfunction "1_1") (pintype "passive"))
      (node (ref "IC1") (pin "14") (pinfunction "NRST_14") (pintype "bidirectional"))
      (node (ref "IC4") (pin "RESET") (pinfunction "RESET_RESET") (pintype "bidirectional"))
      (node (ref "RESET-STM") (pin "3") (pinfunction "3_3") (pintype "passive"))
      (node (ref "RESET-STM") (pin "4") (pinfunction "4_4") (pintype "passive"))
      (node (ref "STM-R1") (pin "1") (pinfunction "1_1") (pintype "passive"))
      (node (ref "SV1") (pin "5") (pinfunction "5_5") (pintype "passive"))
    )
    (net (code "11") (name "DOUT") (class "Default")
      (node (ref "IC1") (pin "90") (pinfunction "PB4_90") (pintype "bidirectional"))
      (node (ref "TO-UNDER") (pin "4") (pinfunction "4_4") (pintype "passive"))
    )
    (net (code "12") (name "DP1") (class "Default")
      (node (ref "IC1") (pin "69") (pinfunction "PA10_69") (pintype "bidirectional"))
      (node (ref "LED1") (pin "5") (pinfunction "DP_5") (pintype "bidirectional"))
    )
    (net (code "13") (name "DP2") (class "Default")
      (node (ref "IC1") (pin "70") (pinfunction "PA11_70") (pintype "bidirectional"))
      (node (ref "LED2") (pin "5") (pinfunction "DP_5") (pintype "bidirectional"))
    )
    (net (code "14") (name "E1") (class "Default")
      (node (ref "IC1") (pin "35") (pinfunction "PB0_35") (pintype "bidirectional"))
      (node (ref "L3") (pin "A") (pinfunction "A_A") (pintype "passive"))
    )
    (net (code "15") (name "E2") (class "Default")
      (node (ref "IC1") (pin "36") (pinfunction "PB1_36") (pintype "bidirectional"))
      (node (ref "L4") (pin "A") (pinfunction "A_A") (pintype "passive"))
    )
    (net (code "16") (name "FET1") (class "Default")
      (node (ref "FET1-R1") (pin "2") (pinfunction "2_2") (pintype "passive"))
      (node (ref "IC1") (pin "95") (pinfunction "PB8_95") (pintype "bidirectional"))
    )
    (net (code "17") (name "FET2") (class "Default")
      (node (ref "FET2-R1") (pin "2") (pinfunction "2_2") (pintype "passive"))
      (node (ref "IC1") (pin "96") (pinfunction "PB9_96") (pintype "bidirectional"))
    )
    (net (code "18") (name "FLED-BLUE") (class "Default")
      (node (ref "IC1") (pin "7") (pinfunction "PC13_7") (pintype "bidirectional"))
      (node (ref "R-B") (pin "1") (pinfunction "1_1") (pintype "passive"))
    )
    (net (code "19") (name "FLED-GREEN") (class "Default")
      (node (ref "IC1") (pin "8") (pinfunction "PC14_8") (pintype "bidirectional"))
      (node (ref "R-G") (pin "1") (pinfunction "1_1") (pintype "passive"))
    )
    (net (code "20") (name "FLED-RED") (class "Default")
      (node (ref "IC1") (pin "9") (pinfunction "PC15_9") (pintype "bidirectional"))
      (node (ref "R-R") (pin "1") (pinfunction "1_1") (pintype "passive"))
    )
    (net (code "21") (name "GATE") (class "Default")
      (node (ref "IC1") (pin "89") (pinfunction "PB3_89") (pintype "bidirectional"))
      (node (ref "TO-UNDER") (pin "5") (pinfunction "5_5") (pintype "passive"))
    )
    (net (code "22") (name "GND") (class "Default")
      (node (ref "3.3C1") (pin "-") (pinfunction "-_-") (pintype "passive"))
      (node (ref "3.3C2") (pin "2") (pinfunction "2_2") (pintype "passive"))
      (node (ref "3.3REG") (pin "3") (pinfunction "GND_1_3") (pintype "bidirectional"))
      (node (ref "3.3REG") (pin "7") (pinfunction "GND_2_7") (pintype "bidirectional"))
      (node (ref "5C1") (pin "-") (pinfunction "-_-") (pintype "passive"))
      (node (ref "5C2") (pin "2") (pinfunction "2_2") (pintype "passive"))
      (node (ref "5VREG") (pin "3") (pinfunction "GND_1_3") (pintype "bidirectional"))
      (node (ref "5VREG") (pin "7") (pinfunction "GND_2_7") (pintype "bidirectional"))
      (node (ref "9C1") (pin "-") (pinfunction "-_-") (pintype "passive"))
      (node (ref "9C2") (pin "2") (pinfunction "2_2") (pintype "passive"))
      (node (ref "C1") (pin "2") (pinfunction "2_2") (pintype "passive"))
      (node (ref "C2") (pin "2") (pinfunction "2_2") (pintype "passive"))
      (node (ref "C3") (pin "2") (pinfunction "2_2") (pintype "passive"))
      (node (ref "C4") (pin "2") (pinfunction "2_2") (pintype "passive"))
      (node (ref "C5") (pin "1") (pinfunction "1_1") (pintype "passive"))
      (node (ref "C6") (pin "1") (pinfunction "1_1") (pintype "passive"))
      (node (ref "CON1") (pin "P$4") (pinfunction "4_P$4") (pintype "bidirectional"))
      (node (ref "CON2") (pin "P$4") (pinfunction "4_P$4") (pintype "bidirectional"))
      (node (ref "ERROR1-R") (pin "1") (pinfunction "1_1") (pintype "passive"))
      (node (ref "ERROR2-R") (pin "1") (pinfunction "1_1") (pintype "passive"))
      (node (ref "FET1") (pin "S") (pinfunction "S_S") (pintype "passive"))
      (node (ref "FET1-R2") (pin "1") (pinfunction "1_1") (pintype "passive"))
      (node (ref "FET2") (pin "S") (pinfunction "S_S") (pintype "passive"))
      (node (ref "FET2-R2") (pin "1") (pinfunction "1_1") (pintype "passive"))
      (node (ref "GND-CH") (pin "1") (pinfunction "P_1") (pintype "passive"))
      (node (ref "GND-CHK") (pin "1") (pinfunction "P_1") (pintype "passive"))
      (node (ref "GND-CHK1") (pin "1") (pinfunction "P_1") (pintype "passive"))
      (node (ref "IC1") (pin "10") (pinfunction "VSS_10") (pintype "power_in"))
      (node (ref "IC1") (pin "20") (pinfunction "VSSA_20") (pintype "power_in"))
      (node (ref "IC1") (pin "27") (pinfunction "VSS_27") (pintype "power_in"))
      (node (ref "IC1") (pin "74") (pinfunction "VSS_74") (pintype "power_in"))
      (node (ref "IC1") (pin "99") (pinfunction "VSS_99") (pintype "power_in"))
      (node (ref "IC2") (pin "5") (pinfunction "I5_5") (pintype "input"))
      (node (ref "IC2") (pin "6") (pinfunction "I6_6") (pintype "input"))
      (node (ref "IC2") (pin "7") (pinfunction "I7_7") (pintype "input"))
      (node (ref "IC2") (pin "8") (pinfunction "GND_8") (pintype "power_in"))
      (node (ref "IC3") (pin "4") (pinfunction "GND_4") (pintype "power_in"))
      (node (ref "IC3") (pin "7") (pinfunction "WP_7") (pintype "input"))
      (node (ref "IC4") (pin "GND") (pinfunction "GND_GND") (pintype "bidirectional"))
      (node (ref "IIC-R") (pin "P$4") (pinfunction "4_P$4") (pintype "bidirectional"))
      (node (ref "JY901") (pin "P$1") (pinfunction "1_P$1") (pintype "bidirectional"))
      (node (ref "LED1") (pin "8") (pinfunction "GND_8") (pintype "bidirectional"))
      (node (ref "LED2") (pin "8") (pinfunction "GND_8") (pintype "bidirectional"))
      (node (ref "M-SW") (pin "3") (pinfunction "S_3") (pintype "passive"))
      (node (ref "MAIN-SPL") (pin "P$2") (pinfunction "2_P$2") (pintype "bidirectional"))
      (node (ref "MAINSW2") (pin "2") (pinfunction "2_2") (pintype "passive"))
      (node (ref "MOTORDRIVER") (pin "13") (pinfunction "13_13") (pintype "passive"))
      (node (ref "Q3") (pin "G") (pinfunction "G_G") (pintype "passive"))
      (node (ref "R1") (pin "2") (pinfunction "2_2") (pintype "passive"))
      (node (ref "R2") (pin "2") (pinfunction "2_2") (pintype "passive"))
      (node (ref "RESET-STM") (pin "1") (pinfunction "1_1") (pintype "passive"))
      (node (ref "RESET-STM") (pin "2") (pinfunction "2_2") (pintype "passive"))
      (node (ref "S1") (pin "1") (pinfunction "1_1") (pintype "bidirectional"))
      (node (ref "S1") (pin "2") (pinfunction "2_2") (pintype "bidirectional"))
      (node (ref "SG1") (pin "2") (pinfunction "2_2") (pintype "passive"))
      (node (ref "SL-R1") (pin "1") (pinfunction "1_1") (pintype "passive"))
      (node (ref "SP-R1") (pin "1") (pinfunction "1_1") (pintype "passive"))
      (node (ref "SP-R3") (pin "1") (pinfunction "1_1") (pintype "passive"))
      (node (ref "SP-SW2") (pin "3") (pinfunction "3_3") (pintype "passive"))
      (node (ref "SP-SW2") (pin "4") (pinfunction "4_4") (pintype "passive"))
      (node (ref "SPI-LCD") (pin "2") (pinfunction "2_2") (pintype "passive"))
      (node (ref "SPI-LCD") (pin "8") (pinfunction "8_8") (pintype "passive"))
      (node (ref "SPI-R") (pin "P$6") (pinfunction "6_P$6") (pintype "bidirectional"))
      (node (ref "STM-C1") (pin "1") (pinfunction "1_1") (pintype "passive"))
      (node (ref "STM-C2") (pin "1") (pinfunction "1_1") (pintype "passive"))
      (node (ref "STM-C3") (pin "1") (pinfunction "1_1") (pintype "passive"))
      (node (ref "STM-C4") (pin "1") (pinfunction "1_1") (pintype "passive"))
      (node (ref "STM-C5") (pin "2") (pinfunction "2_2") (pintype "passive"))
      (node (ref "STM-C6") (pin "2") (pinfunction "2_2") (pintype "passive"))
      (node (ref "STM-R2") (pin "2") (pinfunction "2_2") (pintype "passive"))
      (node (ref "SUOPPLY-SW2") (pin "P$2") (pinfunction "2_P$2") (pintype "bidirectional"))
      (node (ref "SUPPLY3.3V") (pin "2") (pinfunction "KL_2") (pintype "passive"))
      (node (ref "SUPPLY5V") (pin "2") (pinfunction "KL_2") (pintype "passive"))
      (node (ref "SUPPLY9") (pin "2") (pinfunction "KL_2") (pintype "passive"))
      (node (ref "SV1") (pin "3") (pinfunction "3_3") (pintype "passive"))
      (node (ref "TESTSW-R1") (pin "1") (pinfunction "1_1") (pintype "passive"))
      (node (ref "TESTSW-R2") (pin "1") (pinfunction "1_1") (pintype "passive"))
      (node (ref "TESTSW-R3") (pin "1") (pinfunction "1_1") (pintype "passive"))
      (node (ref "TOUCH1") (pin "P$3") (pinfunction "3_P$3") (pintype "bidirectional"))
      (node (ref "TOUCH2") (pin "P$3") (pinfunction "3_P$3") (pintype "bidirectional"))
      (node (ref "TW-SP") (pin "P$1") (pinfunction "1_P$1") (pintype "bidirectional"))
      (node (ref "U$2") (pin "2") (pinfunction "S_2") (pintype "passive"))
      (node (ref "U2") (pin "4") (pinfunction "VSS_4") (pintype "power_in"))
      (node (ref "VOLTAGE-METER1") (pin "P$2") (pinfunction "2_P$2") (pintype "bidirectional"))
      (node (ref "VOLTAGE-METER2") (pin "P$2") (pinfunction "2_P$2") (pintype "bidirectional"))
      (node (ref "X-R2") (pin "1") (pinfunction "1_1") (pintype "passive"))
      (node (ref "X2") (pin "2") (pinfunction "2_2") (pintype "passive"))
      (node (ref "XB1") (pin "10") (pinfunction "GND_10") (pintype "power_in"))
    )
    (net (code "23") (name "LCD-CS") (class "Default")
      (node (ref "IC1") (pin "53") (pinfunction "PB14_53") (pintype "bidirectional"))
      (node (ref "SPI-LCD") (pin "3") (pinfunction "3_3") (pintype "passive"))
    )
    (net (code "24") (name "LCD-RST") (class "Default")
      (node (ref "IC1") (pin "54") (pinfunction "PB15_54") (pintype "bidirectional"))
      (node (ref "SPI-LCD") (pin "4") (pinfunction "4_4") (pintype "passive"))
    )
    (net (code "25") (name "LED-RST") (class "Default")
      (node (ref "IC1") (pin "71") (pinfunction "PA12_71") (pintype "bidirectional"))
      (node (ref "LED1") (pin "2") (pinfunction "RS_2") (pintype "bidirectional"))
      (node (ref "LED2") (pin "2") (pinfunction "RS_2") (pintype "bidirectional"))
      (node (ref "S3") (pin "1") (pinfunction "1_1") (pintype "bidirectional"))
      (node (ref "S3") (pin "2") (pinfunction "2_2") (pintype "bidirectional"))
    )
    (net (code "26") (name "M1CS") (class "Default")
      (node (ref "IC1") (pin "41") (pinfunction "PE10_41") (pintype "bidirectional"))
      (node (ref "MOTORDRIVER") (pin "6") (pinfunction "6_6") (pintype "passive"))
    )
    (net (code "27") (name "M1EN") (class "Default")
      (node (ref "IC1") (pin "38") (pinfunction "PE7_38") (pintype "bidirectional"))
      (node (ref "MOTORDRIVER") (pin "10") (pinfunction "10_10") (pintype "passive"))
    )
    (net (code "28") (name "M1INA") (class "Default")
      (node (ref "IC1") (pin "37") (pinfunction "PB2_37") (pintype "bidirectional"))
      (node (ref "MOTORDRIVER") (pin "9") (pinfunction "9_9") (pintype "passive"))
    )
    (net (code "29") (name "M1INB") (class "Default")
      (node (ref "IC1") (pin "39") (pinfunction "PE8_39") (pintype "bidirectional"))
      (node (ref "MOTORDRIVER") (pin "8") (pinfunction "8_8") (pintype "passive"))
    )
    (net (code "30") (name "M1PWM") (class "Default")
      (node (ref "IC1") (pin "40") (pinfunction "PE9_40") (pintype "bidirectional"))
      (node (ref "MOTORDRIVER") (pin "7") (pinfunction "7_7") (pintype "passive"))
    )
    (net (code "31") (name "M2CS") (class "Default")
      (node (ref "IC1") (pin "46") (pinfunction "PE15_46") (pintype "bidirectional"))
      (node (ref "MOTORDRIVER") (pin "1") (pinfunction "1_1") (pintype "passive"))
    )
    (net (code "32") (name "M2EN") (class "Default")
      (node (ref "IC1") (pin "43") (pinfunction "PE12_43") (pintype "bidirectional"))
      (node (ref "MOTORDRIVER") (pin "5") (pinfunction "5_5") (pintype "passive"))
    )
    (net (code "33") (name "M2INA") (class "Default")
      (node (ref "IC1") (pin "44") (pinfunction "PE13_44") (pintype "bidirectional"))
      (node (ref "MOTORDRIVER") (pin "4") (pinfunction "4_4") (pintype "passive"))
    )
    (net (code "34") (name "M2INB") (class "Default")
      (node (ref "IC1") (pin "45") (pinfunction "PE14_45") (pintype "bidirectional"))
      (node (ref "MOTORDRIVER") (pin "3") (pinfunction "3_3") (pintype "passive"))
    )
    (net (code "35") (name "M2PWM") (class "Default")
      (node (ref "IC1") (pin "42") (pinfunction "PE11_42") (pintype "bidirectional"))
      (node (ref "MOTORDRIVER") (pin "2") (pinfunction "2_2") (pintype "passive"))
    )
    (net (code "36") (name "MISOD") (class "Default")
      (node (ref "IC1") (pin "17") (pinfunction "PC2_17") (pintype "bidirectional"))
      (node (ref "TO-UNDER") (pin "15") (pinfunction "15_15") (pintype "passive"))
    )
    (net (code "37") (name "MISOF") (class "Default")
      (node (ref "IC1") (pin "31") (pinfunction "PA6_31") (pintype "bidirectional"))
      (node (ref "SPI-LCD") (pin "9") (pinfunction "9_9") (pintype "passive"))
      (node (ref "SPI-R") (pin "P$4") (pinfunction "4_P$4") (pintype "bidirectional"))
      (node (ref "U2") (pin "2") (pinfunction "SO_2") (pintype "output"))
    )
    (net (code "38") (name "MOSID") (class "Default")
      (node (ref "IC1") (pin "18") (pinfunction "PC3_18") (pintype "bidirectional"))
      (node (ref "TO-UNDER") (pin "16") (pinfunction "16_16") (pintype "passive"))
    )
    (net (code "39") (name "MOSIF") (class "Default")
      (node (ref "IC1") (pin "32") (pinfunction "PA7_32") (pintype "bidirectional"))
      (node (ref "SPI-LCD") (pin "6") (pinfunction "6_6") (pintype "passive"))
      (node (ref "SPI-R") (pin "P$3") (pinfunction "3_P$3") (pintype "bidirectional"))
      (node (ref "U2") (pin "5") (pinfunction "SI_5") (pintype "input"))
    )
    (net (code "40") (name "MR1A") (class "Default")
      (node (ref "CON1") (pin "P$2") (pinfunction "2_P$2") (pintype "bidirectional"))
      (node (ref "IC1") (pin "23") (pinfunction "PA0_23") (pintype "bidirectional"))
    )
    (net (code "41") (name "MR1B") (class "Default")
      (node (ref "CON1") (pin "P$1") (pinfunction "1_P$1") (pintype "bidirectional"))
      (node (ref "IC1") (pin "24") (pinfunction "PA1_24") (pintype "bidirectional"))
    )
    (net (code "42") (name "MR2A") (class "Default")
      (node (ref "CON2") (pin "P$2") (pinfunction "2_P$2") (pintype "bidirectional"))
      (node (ref "IC1") (pin "63") (pinfunction "PC6_63") (pintype "bidirectional"))
    )
    (net (code "43") (name "MR2B") (class "Default")
      (node (ref "CON2") (pin "P$1") (pinfunction "1_P$1") (pintype "bidirectional"))
      (node (ref "IC1") (pin "64") (pinfunction "PC7_64") (pintype "bidirectional"))
    )
    (net (code "44") (name "MV1") (class "Default")
      (node (ref "IC1") (pin "78") (pinfunction "PC10_78") (pintype "bidirectional"))
      (node (ref "TO-UNDER") (pin "19") (pinfunction "19_19") (pintype "passive"))
    )
    (net (code "45") (name "MV2") (class "Default")
      (node (ref "IC1") (pin "79") (pinfunction "PC11_79") (pintype "bidirectional"))
      (node (ref "TO-UNDER") (pin "18") (pinfunction "18_18") (pintype "passive"))
    )
    (net (code "46") (name "MV3") (class "Default")
      (node (ref "IC1") (pin "80") (pinfunction "PC12_80") (pintype "bidirectional"))
      (node (ref "TO-UNDER") (pin "17") (pinfunction "17_17") (pintype "passive"))
    )
    (net (code "47") (name "MVS1") (class "Default")
      (node (ref "IC1") (pin "3") (pinfunction "PE4_3") (pintype "bidirectional"))
      (node (ref "TO-UNDER") (pin "1") (pinfunction "1_1") (pintype "passive"))
    )
    (net (code "48") (name "MVS2") (class "Default")
      (node (ref "IC1") (pin "2") (pinfunction "PE3_2") (pintype "bidirectional"))
      (node (ref "TO-UNDER") (pin "2") (pinfunction "2_2") (pintype "passive"))
    )
    (net (code "49") (name "MVS3") (class "Default")
      (node (ref "IC1") (pin "1") (pinfunction "PE2_1") (pintype "bidirectional"))
      (node (ref "TO-UNDER") (pin "3") (pinfunction "3_3") (pintype "passive"))
    )
    (net (code "50") (name "Net-(3.3REG-ON{slash}OFF)") (class "Default")
      (node (ref "3.3REG") (pin "1") (pinfunction "ON/OFF_1") (pintype "bidirectional"))
      (node (ref "SP-R4") (pin "1") (pinfunction "1_1") (pintype "passive"))
      (node (ref "SP-SW2") (pin "2") (pinfunction "2_2") (pintype "passive"))
    )
    (net (code "51") (name "Net-(3.3REG-TRIM)") (class "Default")
      (node (ref "3.3REG") (pin "6") (pinfunction "TRIM_6") (pintype "bidirectional"))
      (node (ref "SP-RC2") (pin "3") (pinfunction "E_3") (pintype "passive"))
    )
    (net (code "52") (name "Net-(5VREG-ON{slash}OFF)") (class "Default")
      (node (ref "5VREG") (pin "1") (pinfunction "ON/OFF_1") (pintype "bidirectional"))
      (node (ref "SP-R2") (pin "1") (pinfunction "1_1") (pintype "passive"))
      (node (ref "SP-SW2") (pin "1") (pinfunction "1_1") (pintype "passive"))
    )
    (net (code "53") (name "Net-(5VREG-TRIM)") (class "Default")
      (node (ref "5VREG") (pin "6") (pinfunction "TRIM_6") (pintype "bidirectional"))
      (node (ref "SP-RC1") (pin "3") (pinfunction "E_3") (pintype "passive"))
    )
    (net (code "54") (name "Net-(CHECKLED-PadBLUE)") (class "Default")
      (node (ref "CHECKLED") (pin "BLUE") (pinfunction "BLUE_BLUE") (pintype "bidirectional"))
      (node (ref "R-B") (pin "2") (pinfunction "2_2") (pintype "passive"))
    )
    (net (code "55") (name "Net-(CHECKLED-PadGREEN)") (class "Default")
      (node (ref "CHECKLED") (pin "GREEN") (pinfunction "GREEN_GREEN") (pintype "bidirectional"))
      (node (ref "R-G") (pin "2") (pinfunction "2_2") (pintype "passive"))
    )
    (net (code "56") (name "Net-(CHECKLED-PadRED)") (class "Default")
      (node (ref "CHECKLED") (pin "RED") (pinfunction "RED_RED") (pintype "bidirectional"))
      (node (ref "R-R") (pin "2") (pinfunction "2_2") (pintype "passive"))
    )
    (net (code "57") (name "Net-(FET1-PadG)") (class "Default")
      (node (ref "FET1") (pin "G") (pinfunction "G_G") (pintype "passive"))
      (node (ref "FET1-R1") (pin "1") (pinfunction "1_1") (pintype "passive"))
      (node (ref "FET1-R2") (pin "2") (pinfunction "2_2") (pintype "passive"))
    )
    (net (code "58") (name "Net-(FET2-PadG)") (class "Default")
      (node (ref "FET2") (pin "G") (pinfunction "G_G") (pintype "passive"))
      (node (ref "FET2-R1") (pin "1") (pinfunction "1_1") (pintype "passive"))
      (node (ref "FET2-R2") (pin "2") (pinfunction "2_2") (pintype "passive"))
    )
    (net (code "59") (name "Net-(IC1A-OSC_IN)") (class "Default")
      (node (ref "8MHZ") (pin "2") (pinfunction "2_2") (pintype "passive"))
      (node (ref "C5") (pin "2") (pinfunction "2_2") (pintype "passive"))
      (node (ref "IC1") (pin "12") (pinfunction "OSC_IN_12") (pintype "bidirectional"))
    )
    (net (code "60") (name "Net-(IC1A-OSC_OUT)") (class "Default")
      (node (ref "8MHZ") (pin "1") (pinfunction "1_1") (pintype "passive"))
      (node (ref "C6") (pin "2") (pinfunction "2_2") (pintype "passive"))
      (node (ref "IC1") (pin "13") (pinfunction "OSC_OUT_13") (pintype "bidirectional"))
    )
    (net (code "61") (name "Net-(IC1A-PD12)") (class "Default")
      (node (ref "IC1") (pin "59") (pinfunction "PD12_59") (pintype "bidirectional"))
      (node (ref "IC2") (pin "1") (pinfunction "I1_1") (pintype "input"))
    )
    (net (code "62") (name "Net-(IC1A-PD13)") (class "Default")
      (node (ref "IC1") (pin "60") (pinfunction "PD13_60") (pintype "bidirectional"))
      (node (ref "IC2") (pin "2") (pinfunction "I2_2") (pintype "input"))
    )
    (net (code "63") (name "Net-(IC1A-PD14)") (class "Default")
      (node (ref "IC1") (pin "61") (pinfunction "PD14_61") (pintype "bidirectional"))
      (node (ref "IC2") (pin "3") (pinfunction "I3_3") (pintype "input"))
    )
    (net (code "64") (name "Net-(IC1A-PD15)") (class "Default")
      (node (ref "IC1") (pin "62") (pinfunction "PD15_62") (pintype "bidirectional"))
      (node (ref "IC2") (pin "4") (pinfunction "I4_4") (pintype "input"))
    )
    (net (code "65") (name "Net-(IC1A-VCAP1)") (class "Default")
      (node (ref "IC1") (pin "49") (pinfunction "VCAP1_49") (pintype "power_in"))
      (node (ref "STM-C6") (pin "1") (pinfunction "1_1") (pintype "passive"))
    )
    (net (code "66") (name "Net-(IC1A-VCAP2)") (class "Default")
      (node (ref "IC1") (pin "73") (pinfunction "VCAP2_73") (pintype "power_in"))
      (node (ref "STM-C5") (pin "1") (pinfunction "1_1") (pintype "passive"))
    )
    (net (code "67") (name "Net-(IC2-O1)") (class "Default")
      (node (ref "IC2") (pin "16") (pinfunction "O1_16") (pintype "open_collector"))
      (node (ref "J1") (pin "P$2") (pinfunction "2_P$2") (pintype "bidirectional"))
      (node (ref "STEPINDI1") (pin "C") (pinfunction "C_C") (pintype "passive"))
    )
    (net (code "68") (name "Net-(IC2-O2)") (class "Default")
      (node (ref "IC2") (pin "15") (pinfunction "O2_15") (pintype "open_collector"))
      (node (ref "J1") (pin "P$3") (pinfunction "3_P$3") (pintype "bidirectional"))
      (node (ref "STEPINDI2") (pin "C") (pinfunction "C_C") (pintype "passive"))
    )
    (net (code "69") (name "Net-(IC2-O3)") (class "Default")
      (node (ref "IC2") (pin "14") (pinfunction "O3_14") (pintype "open_collector"))
      (node (ref "J1") (pin "P$4") (pinfunction "4_P$4") (pintype "bidirectional"))
      (node (ref "STEPINDI3") (pin "C") (pinfunction "C_C") (pintype "passive"))
    )
    (net (code "70") (name "Net-(IC2-O4)") (class "Default")
      (node (ref "IC2") (pin "13") (pinfunction "O4_13") (pintype "open_collector"))
      (node (ref "J1") (pin "P$5") (pinfunction "5_P$5") (pintype "bidirectional"))
      (node (ref "STEPINDI4") (pin "C") (pinfunction "C_C") (pintype "passive"))
    )
    (net (code "71") (name "Net-(INDILED1-Pad1)") (class "Default")
      (node (ref "INDILED1") (pin "1") (pinfunction "1_1") (pintype "passive"))
      (node (ref "STEPINDI1") (pin "A") (pinfunction "A_A") (pintype "passive"))
    )
    (net (code "72") (name "Net-(INDILED2-Pad1)") (class "Default")
      (node (ref "INDILED2") (pin "1") (pinfunction "1_1") (pintype "passive"))
      (node (ref "STEPINDI2") (pin "A") (pinfunction "A_A") (pintype "passive"))
    )
    (net (code "73") (name "Net-(INDILED3-Pad1)") (class "Default")
      (node (ref "INDILED3") (pin "1") (pinfunction "1_1") (pintype "passive"))
      (node (ref "STEPINDI3") (pin "A") (pinfunction "A_A") (pintype "passive"))
    )
    (net (code "74") (name "Net-(INDILED4-Pad1)") (class "Default")
      (node (ref "INDILED4") (pin "1") (pinfunction "1_1") (pintype "passive"))
      (node (ref "STEPINDI4") (pin "A") (pinfunction "A_A") (pintype "passive"))
    )
    (net (code "75") (name "Net-(L3-C)") (class "Default")
      (node (ref "ERROR1-R") (pin "2") (pinfunction "2_2") (pintype "passive"))
      (node (ref "L3") (pin "K") (pinfunction "C_K") (pintype "passive"))
    )
    (net (code "76") (name "Net-(L4-C)") (class "Default")
      (node (ref "ERROR2-R") (pin "2") (pinfunction "2_2") (pintype "passive"))
      (node (ref "L4") (pin "K") (pinfunction "C_K") (pintype "passive"))
    )
    (net (code "77") (name "Net-(LED1-CO)") (class "Default")
      (node (ref "LED1") (pin "4") (pinfunction "CO_4") (pintype "bidirectional"))
      (node (ref "LED2") (pin "9") (pinfunction "CL_9") (pintype "bidirectional"))
    )
    (net (code "78") (name "Net-(LEDSP2B-KL)") (class "Default")
      (node (ref "FET2") (pin "D") (pinfunction "D_D") (pintype "passive"))
      (node (ref "LEDSP2") (pin "2") (pinfunction "KL_2") (pintype "passive"))
    )
    (net (code "79") (name "Net-(LEDSPB-KL)") (class "Default")
      (node (ref "FET1") (pin "D") (pinfunction "D_D") (pintype "passive"))
      (node (ref "LEDSP") (pin "2") (pinfunction "KL_2") (pintype "passive"))
    )
    (net (code "80") (name "Net-(M-SW-O)") (class "Default")
      (node (ref "M-SW") (pin "1") (pinfunction "O_1") (pintype "passive"))
      (node (ref "SP-R5") (pin "1") (pinfunction "1_1") (pintype "passive"))
    )
    (net (code "81") (name "Net-(M-SW-P)") (class "Default")
      (node (ref "M-SW") (pin "2") (pinfunction "P_2") (pintype "passive"))
      (node (ref "Q4") (pin "G") (pinfunction "G_G") (pintype "passive"))
    )
    (net (code "82") (name "Net-(Q3-PadS)") (class "Default")
      (node (ref "Q3") (pin "S") (pinfunction "S_S") (pintype "passive"))
      (node (ref "Q5") (pin "S") (pinfunction "S_S") (pintype "passive"))
      (node (ref "SP-R6") (pin "2") (pinfunction "2_2") (pintype "passive"))
    )
    (net (code "83") (name "Net-(S2-P)") (class "Default")
      (node (ref "S2") (pin "2") (pinfunction "P_2") (pintype "passive"))
      (node (ref "VOLTAGE-METER2") (pin "P$1") (pinfunction "1_P$1") (pintype "bidirectional"))
    )
    (net (code "84") (name "Net-(SL-R1-Pad2)") (class "Default")
      (node (ref "SL-R1") (pin "2") (pinfunction "2_2") (pintype "passive"))
      (node (ref "SP-LED") (pin "C") (pinfunction "C_C") (pintype "passive"))
    )
    (net (code "85") (name "Net-(SP-RC1-A)") (class "Default")
      (node (ref "SP-R1") (pin "2") (pinfunction "2_2") (pintype "passive"))
      (node (ref "SP-RC1") (pin "1") (pinfunction "A_1") (pintype "passive"))
      (node (ref "SP-RC1") (pin "2") (pinfunction "S_2") (pintype "passive"))
    )
    (net (code "86") (name "Net-(SP-RC2-A)") (class "Default")
      (node (ref "SP-R3") (pin "2") (pinfunction "2_2") (pintype "passive"))
      (node (ref "SP-RC2") (pin "1") (pinfunction "A_1") (pintype "passive"))
      (node (ref "SP-RC2") (pin "2") (pinfunction "S_2") (pintype "passive"))
    )
    (net (code "87") (name "Net-(SUOPPLY-SW2-1)") (class "Default")
      (node (ref "MAINSW2") (pin "1") (pinfunction "1_1") (pintype "passive"))
      (node (ref "Q5") (pin "G") (pinfunction "G_G") (pintype "passive"))
      (node (ref "SP-R6") (pin "1") (pinfunction "1_1") (pintype "passive"))
      (node (ref "SUOPPLY-SW2") (pin "P$1") (pinfunction "1_P$1") (pintype "bidirectional"))
    )
    (net (code "88") (name "Net-(SUPPLY9A-KL)") (class "Default")
      (node (ref "Q3") (pin "D") (pinfunction "D_D") (pintype "passive"))
      (node (ref "SUPPLY9") (pin "1") (pinfunction "KL_1") (pintype "passive"))
      (node (ref "X2") (pin "1") (pinfunction "1_1") (pintype "passive"))
    )
    (net (code "89") (name "Net-(U$2A-S)") (class "Default")
      (node (ref "Q4") (pin "D") (pinfunction "D_D") (pintype "passive"))
      (node (ref "U$2") (pin "1") (pinfunction "S_1") (pintype "passive"))
    )
    (net (code "90") (name "Net-(XB1-AD0{slash}DIO0)") (class "Default")
      (node (ref "DIO0-JP") (pin "2") (pinfunction "2_2") (pintype "passive"))
      (node (ref "XB1") (pin "20") (pinfunction "AD0/DIO0_20") (pintype "bidirectional"))
    )
    (net (code "91") (name "Net-(XB1-AD1{slash}DIO1)") (class "Default")
      (node (ref "DIO1-JP") (pin "2") (pinfunction "2_2") (pintype "passive"))
      (node (ref "XB1") (pin "19") (pinfunction "AD1/DIO1_19") (pintype "bidirectional"))
    )
    (net (code "92") (name "Net-(XB1-~{RESET})") (class "Default")
      (node (ref "S1") (pin "3") (pinfunction "3_3") (pintype "bidirectional"))
      (node (ref "S1") (pin "4") (pinfunction "4_4") (pintype "bidirectional"))
      (node (ref "XB1") (pin "5") (pinfunction "~{RESET}_5") (pintype "input"))
      (node (ref "XBEE-RST") (pin "1") (pinfunction "1_1") (pintype "passive"))
    )
    (net (code "93") (name "PING1") (class "Default")
      (node (ref "IC1") (pin "81") (pinfunction "PD0_81") (pintype "bidirectional"))
      (node (ref "TO-UNDER") (pin "13") (pinfunction "13_13") (pintype "passive"))
    )
    (net (code "94") (name "PING2") (class "Default")
      (node (ref "IC1") (pin "82") (pinfunction "PD1_82") (pintype "bidirectional"))
      (node (ref "TO-UNDER") (pin "12") (pinfunction "12_12") (pintype "passive"))
    )
    (net (code "95") (name "PING3") (class "Default")
      (node (ref "IC1") (pin "83") (pinfunction "PD2_83") (pintype "bidirectional"))
      (node (ref "TO-UNDER") (pin "11") (pinfunction "11_11") (pintype "passive"))
    )
    (net (code "96") (name "PING4") (class "Default")
      (node (ref "IC1") (pin "84") (pinfunction "PD3_84") (pintype "bidirectional"))
      (node (ref "TO-UNDER") (pin "10") (pinfunction "10_10") (pintype "passive"))
    )
    (net (code "97") (name "PING5") (class "Default")
      (node (ref "IC1") (pin "85") (pinfunction "PD4_85") (pintype "bidirectional"))
      (node (ref "TO-UNDER") (pin "9") (pinfunction "9_9") (pintype "passive"))
    )
    (net (code "98") (name "PING6") (class "Default")
      (node (ref "IC1") (pin "86") (pinfunction "PD5_86") (pintype "bidirectional"))
      (node (ref "TO-UNDER") (pin "8") (pinfunction "8_8") (pintype "passive"))
    )
    (net (code "99") (name "RAM-CS") (class "Default")
      (node (ref "IC1") (pin "4") (pinfunction "PE5_4") (pintype "bidirectional"))
      (node (ref "SRAM-R1") (pin "1") (pinfunction "1_1") (pintype "passive"))
      (node (ref "U2") (pin "1") (pinfunction "~{CS}_1") (pintype "input"))
    )
    (net (code "100") (name "RAM-HOLD") (class "Default")
      (node (ref "IC1") (pin "29") (pinfunction "PA4_29") (pintype "bidirectional"))
      (node (ref "SRAM-R2") (pin "1") (pinfunction "1_1") (pintype "passive"))
      (node (ref "U2") (pin "7") (pinfunction "~{HOLD}_7") (pintype "input"))
    )
    (net (code "101") (name "RANGE") (class "Default")
      (node (ref "IC1") (pin "87") (pinfunction "PD6_87") (pintype "bidirectional"))
      (node (ref "TO-UNDER") (pin "7") (pinfunction "7_7") (pintype "passive"))
    )
    (net (code "102") (name "SCKD") (class "Default")
      (node (ref "IC1") (pin "52") (pinfunction "PB13_52") (pintype "bidirectional"))
      (node (ref "TO-UNDER") (pin "14") (pinfunction "14_14") (pintype "passive"))
    )
    (net (code "103") (name "SCKF") (class "Default")
      (node (ref "IC1") (pin "30") (pinfunction "PA5_30") (pintype "bidirectional"))
      (node (ref "SPI-LCD") (pin "7") (pinfunction "7_7") (pintype "passive"))
      (node (ref "SPI-R") (pin "P$2") (pinfunction "2_P$2") (pintype "bidirectional"))
      (node (ref "U2") (pin "6") (pinfunction "SCK_6") (pintype "input"))
    )
    (net (code "104") (name "SCL-C") (class "Default")
      (node (ref "I2C-R1") (pin "1") (pinfunction "1_1") (pintype "passive"))
      (node (ref "IC1") (pin "47") (pinfunction "PB10_47") (pintype "bidirectional"))
      (node (ref "IC3") (pin "6") (pinfunction "SCL_6") (pintype "bidirectional"))
      (node (ref "IIC-R") (pin "P$1") (pinfunction "1_P$1") (pintype "bidirectional"))
      (node (ref "JY901") (pin "P$2") (pinfunction "2_P$2") (pintype "bidirectional"))
    )
    (net (code "105") (name "SCL-D") (class "Default")
      (node (ref "IC1") (pin "67") (pinfunction "PA8_67") (pintype "bidirectional"))
      (node (ref "IC4") (pin "SCL") (pinfunction "SCL_SCL") (pintype "bidirectional"))
      (node (ref "TO-UNDER") (pin "20") (pinfunction "20_20") (pintype "passive"))
    )
    (net (code "106") (name "SDA-C") (class "Default")
      (node (ref "I2C-R2") (pin "1") (pinfunction "1_1") (pintype "passive"))
      (node (ref "IC1") (pin "48") (pinfunction "PB11_48") (pintype "bidirectional"))
      (node (ref "IC3") (pin "5") (pinfunction "SDA_5") (pintype "bidirectional"))
      (node (ref "IIC-R") (pin "P$2") (pinfunction "2_P$2") (pintype "bidirectional"))
      (node (ref "JY901") (pin "P$3") (pinfunction "3_P$3") (pintype "bidirectional"))
    )
    (net (code "107") (name "SDA-D") (class "Default")
      (node (ref "IC1") (pin "66") (pinfunction "PC9_66") (pintype "bidirectional"))
      (node (ref "IC4") (pin "SDA") (pinfunction "SDA_SDA") (pintype "bidirectional"))
      (node (ref "TO-UNDER") (pin "21") (pinfunction "21_21") (pintype "passive"))
    )
    (net (code "108") (name "SS-R") (class "Default")
      (node (ref "IC1") (pin "5") (pinfunction "PE6_5") (pintype "bidirectional"))
      (node (ref "SPI-R") (pin "P$5") (pinfunction "5_P$5") (pintype "bidirectional"))
    )
    (net (code "109") (name "SW1") (class "Default")
      (node (ref "IC1") (pin "55") (pinfunction "PD8_55") (pintype "bidirectional"))
      (node (ref "TESTSW-R1") (pin "2") (pinfunction "2_2") (pintype "passive"))
      (node (ref "XMEGA-TEST1") (pin "3") (pinfunction "3_3") (pintype "passive"))
      (node (ref "XMEGA-TEST1") (pin "4") (pinfunction "4_4") (pintype "passive"))
    )
    (net (code "110") (name "SW2") (class "Default")
      (node (ref "IC1") (pin "56") (pinfunction "PD9_56") (pintype "bidirectional"))
      (node (ref "TESTSW-R2") (pin "2") (pinfunction "2_2") (pintype "passive"))
      (node (ref "XMEGA-TEST2") (pin "3") (pinfunction "3_3") (pintype "passive"))
      (node (ref "XMEGA-TEST2") (pin "4") (pinfunction "4_4") (pintype "passive"))
    )
    (net (code "111") (name "SW3") (class "Default")
      (node (ref "IC1") (pin "57") (pinfunction "PD10_57") (pintype "bidirectional"))
      (node (ref "TESTSW-R3") (pin "2") (pinfunction "2_2") (pintype "passive"))
      (node (ref "XMEGA-TEST3") (pin "3") (pinfunction "3_3") (pintype "passive"))
      (node (ref "XMEGA-TEST3") (pin "4") (pinfunction "4_4") (pintype "passive"))
    )
    (net (code "112") (name "SWCLK") (class "Default")
      (node (ref "IC1") (pin "76") (pinfunction "PA14_76") (pintype "bidirectional"))
      (node (ref "SV1") (pin "2") (pinfunction "2_2") (pintype "passive"))
    )
    (net (code "113") (name "SWDIO") (class "Default")
      (node (ref "IC1") (pin "72") (pinfunction "PA13_72") (pintype "bidirectional"))
      (node (ref "SV1") (pin "4") (pinfunction "4_4") (pintype "passive"))
    )
    (net (code "114") (name "TOUCH1") (class "Default")
      (node (ref "IC1") (pin "15") (pinfunction "PC0_15") (pintype "bidirectional"))
      (node (ref "TOUCH1") (pin "P$1") (pinfunction "1_P$1") (pintype "bidirectional"))
    )
    (net (code "115") (name "TOUCH2") (class "Default")
      (node (ref "IC1") (pin "16") (pinfunction "PC1_16") (pintype "bidirectional"))
      (node (ref "TOUCH2") (pin "P$1") (pinfunction "1_P$1") (pintype "bidirectional"))
    )
    (net (code "116") (name "USART1-RX") (class "Default")
      (node (ref "IC1") (pin "93") (pinfunction "PB7_93") (pintype "bidirectional"))
      (node (ref "XB1") (pin "2") (pinfunction "DOUT_2") (pintype "output"))
    )
    (net (code "117") (name "USART1-TX") (class "Default")
      (node (ref "IC1") (pin "92") (pinfunction "PB6_92") (pintype "bidirectional"))
      (node (ref "XB1") (pin "3") (pinfunction "DIN/~{CONFIG}_3") (pintype "input"))
    )
    (net (code "118") (name "USART2RX") (class "Default")
      (node (ref "IC1") (pin "26") (pinfunction "PA3_26") (pintype "bidirectional"))
      (node (ref "TWILITE") (pin "4") (pinfunction "4_4") (pintype "passive"))
    )
    (net (code "119") (name "USART2TX") (class "Default")
      (node (ref "IC1") (pin "25") (pinfunction "PA2_25") (pintype "bidirectional"))
      (node (ref "TWILITE") (pin "2") (pinfunction "2_2") (pintype "passive"))
    )
    (net (code "120") (name "unconnected-(3.3REG-NC_1-Pad8)") (class "Default")
      (node (ref "3.3REG") (pin "8") (pinfunction "NC_1_8") (pintype "bidirectional"))
    )
    (net (code "121") (name "unconnected-(3.3REG-NC_2-Pad11)") (class "Default")
      (node (ref "3.3REG") (pin "11") (pinfunction "NC_2_11") (pintype "bidirectional"))
    )
    (net (code "122") (name "unconnected-(3.3REG-NC_3-Pad12)") (class "Default")
      (node (ref "3.3REG") (pin "12") (pinfunction "NC_3_12") (pintype "bidirectional"))
    )
    (net (code "123") (name "unconnected-(3.3REG-PGOOD-Pad10)") (class "Default")
      (node (ref "3.3REG") (pin "10") (pinfunction "PGOOD_10") (pintype "bidirectional"))
    )
    (net (code "124") (name "unconnected-(3.3REG-SEQ-Pad9)") (class "Default")
      (node (ref "3.3REG") (pin "9") (pinfunction "SEQ_9") (pintype "bidirectional"))
    )
    (net (code "125") (name "unconnected-(5VREG-NC_1-Pad8)") (class "Default")
      (node (ref "5VREG") (pin "8") (pinfunction "NC_1_8") (pintype "bidirectional"))
    )
    (net (code "126") (name "unconnected-(5VREG-NC_2-Pad11)") (class "Default")
      (node (ref "5VREG") (pin "11") (pinfunction "NC_2_11") (pintype "bidirectional"))
    )
    (net (code "127") (name "unconnected-(5VREG-NC_3-Pad12)") (class "Default")
      (node (ref "5VREG") (pin "12") (pinfunction "NC_3_12") (pintype "bidirectional"))
    )
    (net (code "128") (name "unconnected-(5VREG-PGOOD-Pad10)") (class "Default")
      (node (ref "5VREG") (pin "10") (pinfunction "PGOOD_10") (pintype "bidirectional"))
    )
    (net (code "129") (name "unconnected-(5VREG-SEQ-Pad9)") (class "Default")
      (node (ref "5VREG") (pin "9") (pinfunction "SEQ_9") (pintype "bidirectional"))
    )
    (net (code "130") (name "unconnected-(IC1A-PA9-Pad68)") (class "Default")
      (node (ref "IC1") (pin "68") (pinfunction "PA9_68") (pintype "bidirectional"))
    )
    (net (code "131") (name "unconnected-(IC1A-PB5-Pad91)") (class "Default")
      (node (ref "IC1") (pin "91") (pinfunction "PB5_91") (pintype "bidirectional"))
    )
    (net (code "132") (name "unconnected-(IC1A-PB12-Pad51)") (class "Default")
      (node (ref "IC1") (pin "51") (pinfunction "PB12_51") (pintype "bidirectional"))
    )
    (net (code "133") (name "unconnected-(IC1A-PC4-Pad33)") (class "Default")
      (node (ref "IC1") (pin "33") (pinfunction "PC4_33") (pintype "bidirectional"))
    )
    (net (code "134") (name "unconnected-(IC1A-PC5-Pad34)") (class "Default")
      (node (ref "IC1") (pin "34") (pinfunction "PC5_34") (pintype "bidirectional"))
    )
    (net (code "135") (name "unconnected-(IC1A-PD11-Pad58)") (class "Default")
      (node (ref "IC1") (pin "58") (pinfunction "PD11_58") (pintype "bidirectional"))
    )
    (net (code "136") (name "unconnected-(IC1A-PE0-Pad97)") (class "Default")
      (node (ref "IC1") (pin "97") (pinfunction "PE0_97") (pintype "bidirectional"))
    )
    (net (code "137") (name "unconnected-(IC1A-PE1-Pad98)") (class "Default")
      (node (ref "IC1") (pin "98") (pinfunction "PE1_98") (pintype "bidirectional"))
    )
    (net (code "138") (name "unconnected-(IC2-O5-Pad12)") (class "Default")
      (node (ref "IC2") (pin "12") (pinfunction "O5_12") (pintype "open_collector"))
    )
    (net (code "139") (name "unconnected-(IC2-O6-Pad11)") (class "Default")
      (node (ref "IC2") (pin "11") (pinfunction "O6_11") (pintype "open_collector"))
    )
    (net (code "140") (name "unconnected-(IC2-O7-Pad10)") (class "Default")
      (node (ref "IC2") (pin "10") (pinfunction "O7_10") (pintype "open_collector"))
    )
    (net (code "141") (name "unconnected-(LED1-CD-Pad7)") (class "Default")
      (node (ref "LED1") (pin "7") (pinfunction "CD_7") (pintype "bidirectional"))
    )
    (net (code "142") (name "unconnected-(LED1-DI-Pad10)") (class "Default")
      (node (ref "LED1") (pin "10") (pinfunction "DI_10") (pintype "bidirectional"))
    )
    (net (code "143") (name "unconnected-(LED1-DO-Pad6)") (class "Default")
      (node (ref "LED1") (pin "6") (pinfunction "DO_6") (pintype "bidirectional"))
    )
    (net (code "144") (name "unconnected-(LED1-UCG-Pad3)") (class "Default")
      (node (ref "LED1") (pin "3") (pinfunction "UCG_3") (pintype "bidirectional"))
    )
    (net (code "145") (name "unconnected-(LED2-CD-Pad7)") (class "Default")
      (node (ref "LED2") (pin "7") (pinfunction "CD_7") (pintype "bidirectional"))
    )
    (net (code "146") (name "unconnected-(LED2-CO-Pad4)") (class "Default")
      (node (ref "LED2") (pin "4") (pinfunction "CO_4") (pintype "bidirectional"))
    )
    (net (code "147") (name "unconnected-(LED2-DI-Pad10)") (class "Default")
      (node (ref "LED2") (pin "10") (pinfunction "DI_10") (pintype "bidirectional"))
    )
    (net (code "148") (name "unconnected-(LED2-DO-Pad6)") (class "Default")
      (node (ref "LED2") (pin "6") (pinfunction "DO_6") (pintype "bidirectional"))
    )
    (net (code "149") (name "unconnected-(LED2-UCG-Pad3)") (class "Default")
      (node (ref "LED2") (pin "3") (pinfunction "UCG_3") (pintype "bidirectional"))
    )
    (net (code "150") (name "unconnected-(MAINSW2-Pad3)") (class "Default")
      (node (ref "MAINSW2") (pin "3") (pinfunction "3_3") (pintype "passive"))
    )
    (net (code "151") (name "unconnected-(MOTORDRIVER-Pad12)") (class "Default")
      (node (ref "MOTORDRIVER") (pin "12") (pinfunction "12_12") (pintype "passive"))
    )
    (net (code "152") (name "unconnected-(MOTORDRIVER-Pad14)") (class "Default")
      (node (ref "MOTORDRIVER") (pin "14") (pinfunction "14_14") (pintype "passive"))
    )
    (net (code "153") (name "unconnected-(SPI-LCD-Pad5)") (class "Default")
      (node (ref "SPI-LCD") (pin "5") (pinfunction "5_5") (pintype "passive"))
    )
    (net (code "154") (name "unconnected-(SUOPPLY-SW2-3-PadP$3)") (class "Default")
      (node (ref "SUOPPLY-SW2") (pin "P$3") (pinfunction "3_P$3") (pintype "bidirectional"))
    )
    (net (code "155") (name "unconnected-(SV1-Pad6)") (class "Default")
      (node (ref "SV1") (pin "6") (pinfunction "6_6") (pintype "passive"))
    )
    (net (code "156") (name "unconnected-(TO-UNDER-Pad22)") (class "Default")
      (node (ref "TO-UNDER") (pin "22") (pinfunction "22_22") (pintype "passive"))
    )
    (net (code "157") (name "unconnected-(TO-UNDER-Pad23)") (class "Default")
      (node (ref "TO-UNDER") (pin "23") (pinfunction "23_23") (pintype "passive"))
    )
    (net (code "158") (name "unconnected-(TWILITE-Pad1)") (class "Default")
      (node (ref "TWILITE") (pin "1") (pinfunction "1_1") (pintype "passive"))
    )
    (net (code "159") (name "unconnected-(TWILITE-Pad3)") (class "Default")
      (node (ref "TWILITE") (pin "3") (pinfunction "3_3") (pintype "passive"))
    )
    (net (code "160") (name "unconnected-(TWILITE-Pad5)") (class "Default")
      (node (ref "TWILITE") (pin "5") (pinfunction "5_5") (pintype "passive"))
    )
    (net (code "161") (name "unconnected-(X2-Pad3)") (class "Default")
      (node (ref "X2") (pin "3") (pinfunction "3_3") (pintype "passive"))
    )
    (net (code "162") (name "unconnected-(XB1-AD2{slash}DIO2-Pad18)") (class "Default")
      (node (ref "XB1") (pin "18") (pinfunction "AD2/DIO2_18") (pintype "bidirectional"))
    )
    (net (code "163") (name "unconnected-(XB1-ASSOC{slash}AD5{slash}DIO5-Pad15)") (class "Default")
      (node (ref "XB1") (pin "15") (pinfunction "ASSOC/AD5/DIO5_15") (pintype "bidirectional"))
    )
    (net (code "164") (name "unconnected-(XB1-CD{slash}DOUT_EN{slash}DO8-Pad4)") (class "Default")
      (node (ref "XB1") (pin "4") (pinfunction "CD/DOUT_EN/DO8_4") (pintype "output"))
    )
    (net (code "165") (name "unconnected-(XB1-COORD_SEL{slash}AD3{slash}DIO3-Pad17)") (class "Default")
      (node (ref "XB1") (pin "17") (pinfunction "COORD_SEL/AD3/DIO3_17") (pintype "bidirectional"))
    )
    (net (code "166") (name "unconnected-(XB1-ON{slash}~{SLEEP}-Pad13)") (class "Default")
      (node (ref "XB1") (pin "13") (pinfunction "ON/~{SLEEP}_13") (pintype "output"))
    )
    (net (code "167") (name "unconnected-(XB1-PWM0{slash}RSSI-Pad6)") (class "Default")
      (node (ref "XB1") (pin "6") (pinfunction "PWM0/RSSI_6") (pintype "output"))
    )
    (net (code "168") (name "unconnected-(XB1-RF_TX{slash}AD4{slash}DIO4-Pad11)") (class "Default")
      (node (ref "XB1") (pin "11") (pinfunction "RF_TX/AD4/DIO4_11") (pintype "bidirectional"))
    )
    (net (code "169") (name "unconnected-(XB1-~{CTS}{slash}DIO7-Pad12)") (class "Default")
      (node (ref "XB1") (pin "12") (pinfunction "~{CTS}/DIO7_12") (pintype "bidirectional"))
    )
    (net (code "170") (name "unconnected-(XB1-~{DTR}{slash}SLEEP_RQ{slash}DI8-Pad9)") (class "Default")
      (node (ref "XB1") (pin "9") (pinfunction "~{DTR}/SLEEP_RQ/DI8_9") (pintype "bidirectional"))
    )
    (net (code "171") (name "unconnected-(XB1-~{RTS}{slash}AD6{slash}DIO6-Pad16)") (class "Default")
      (node (ref "XB1") (pin "16") (pinfunction "~{RTS}/AD6/DIO6_16") (pintype "bidirectional"))
    )
  )
)
